# GFB_Sensorknoten.net
KiCad netlist of a schematic drawn in EAGLE
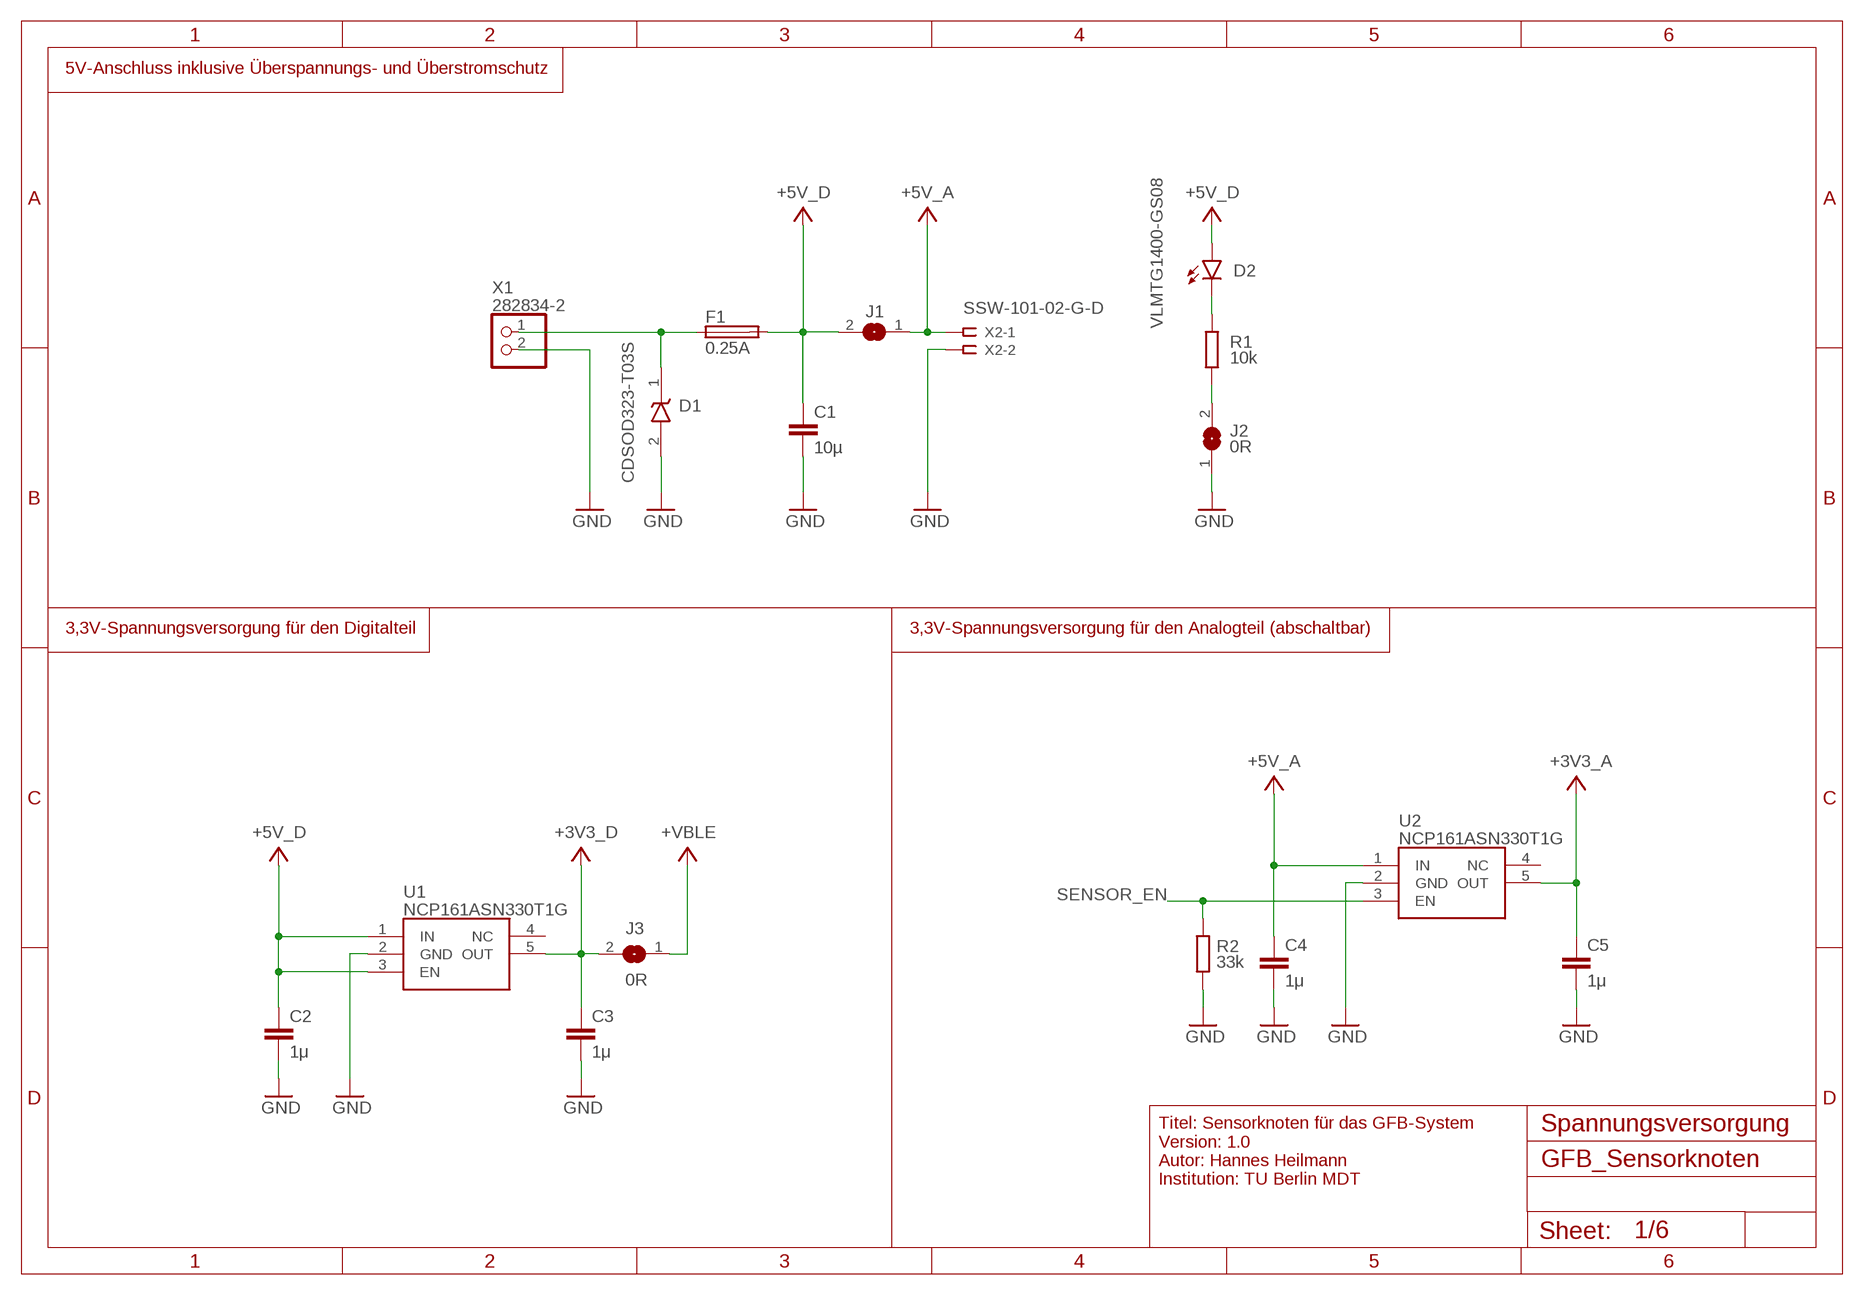
[diagram p0: schematic, sheet 1]
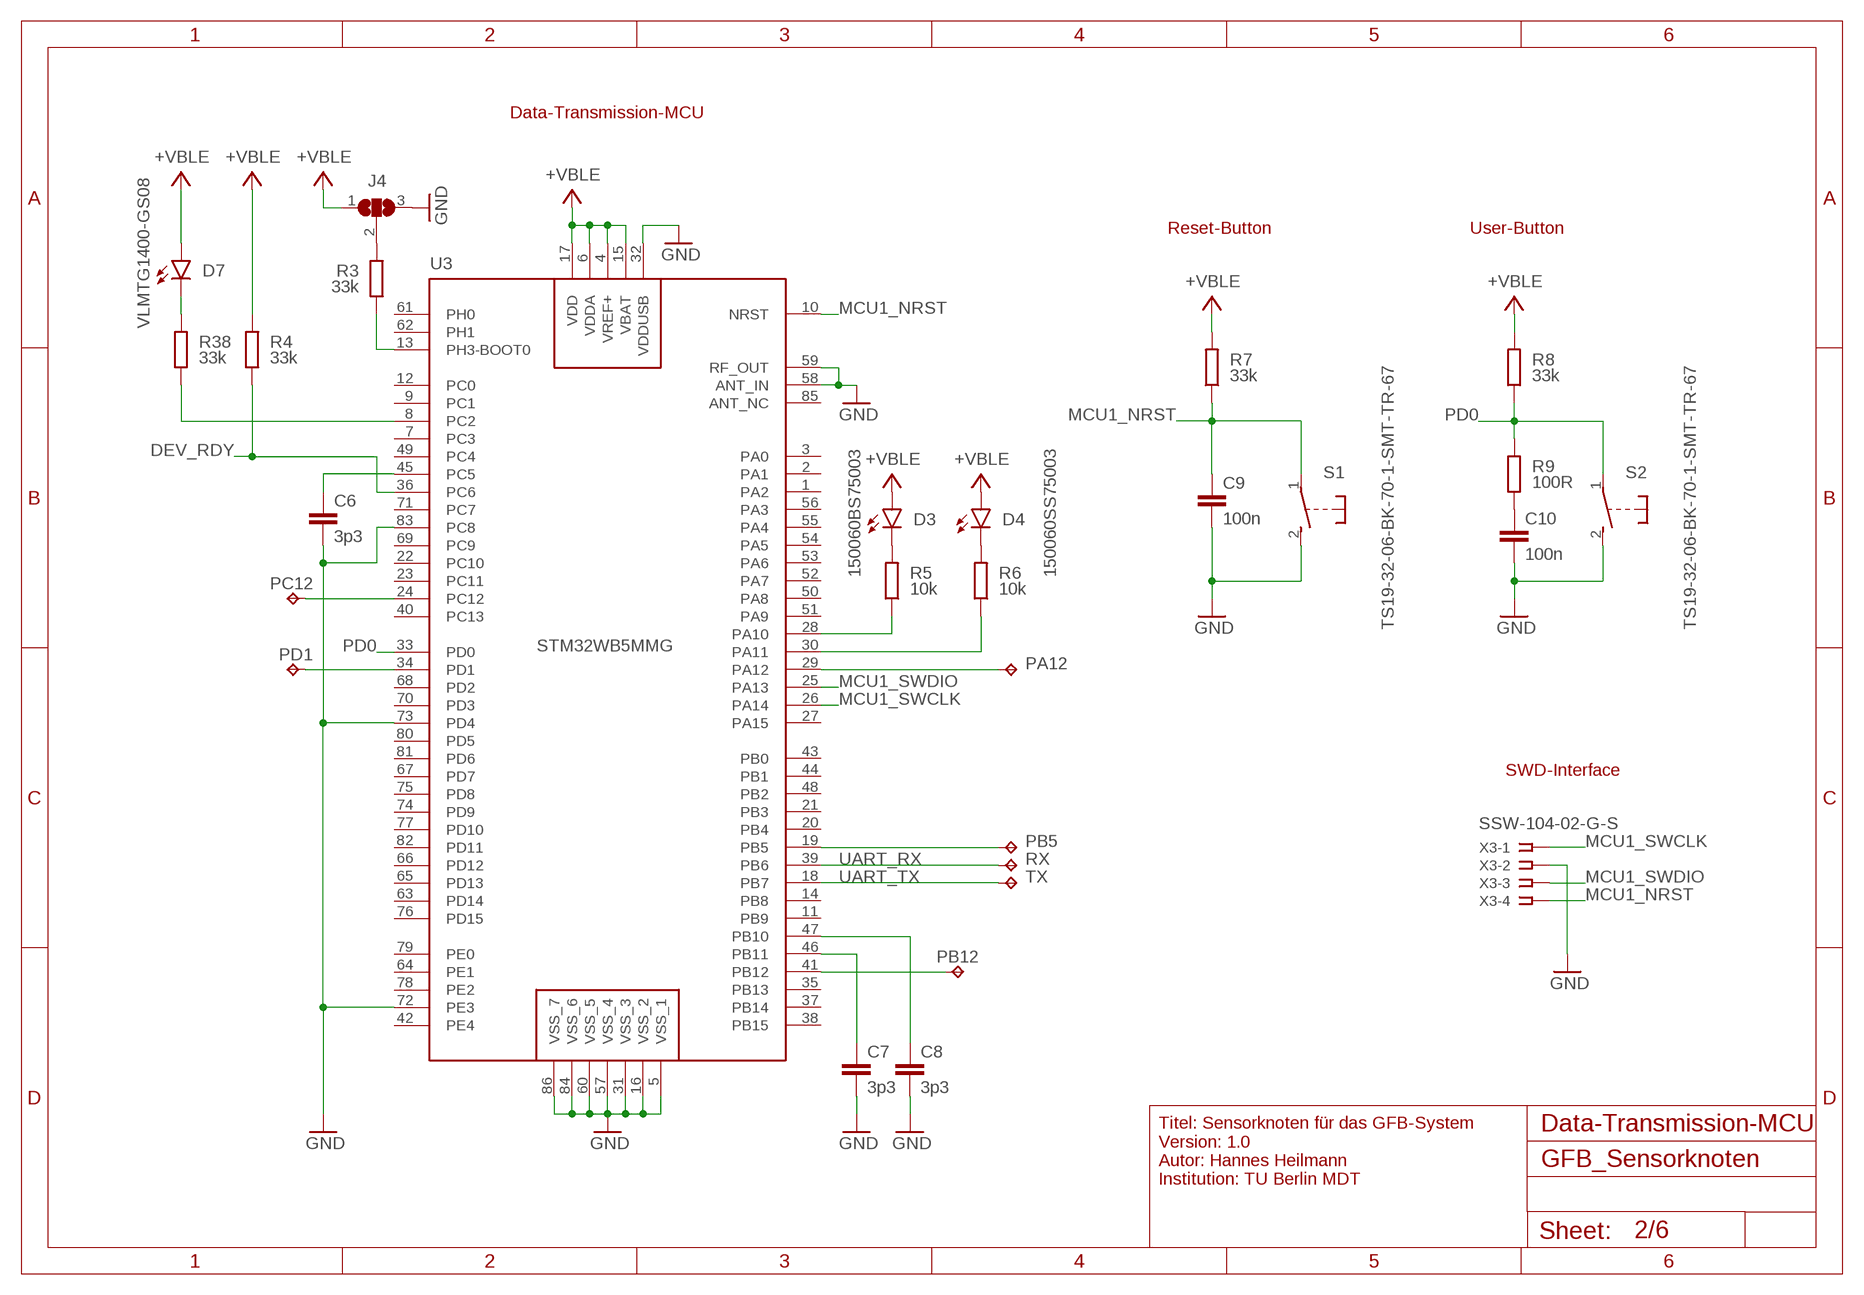
[diagram p1: schematic, sheet 2]
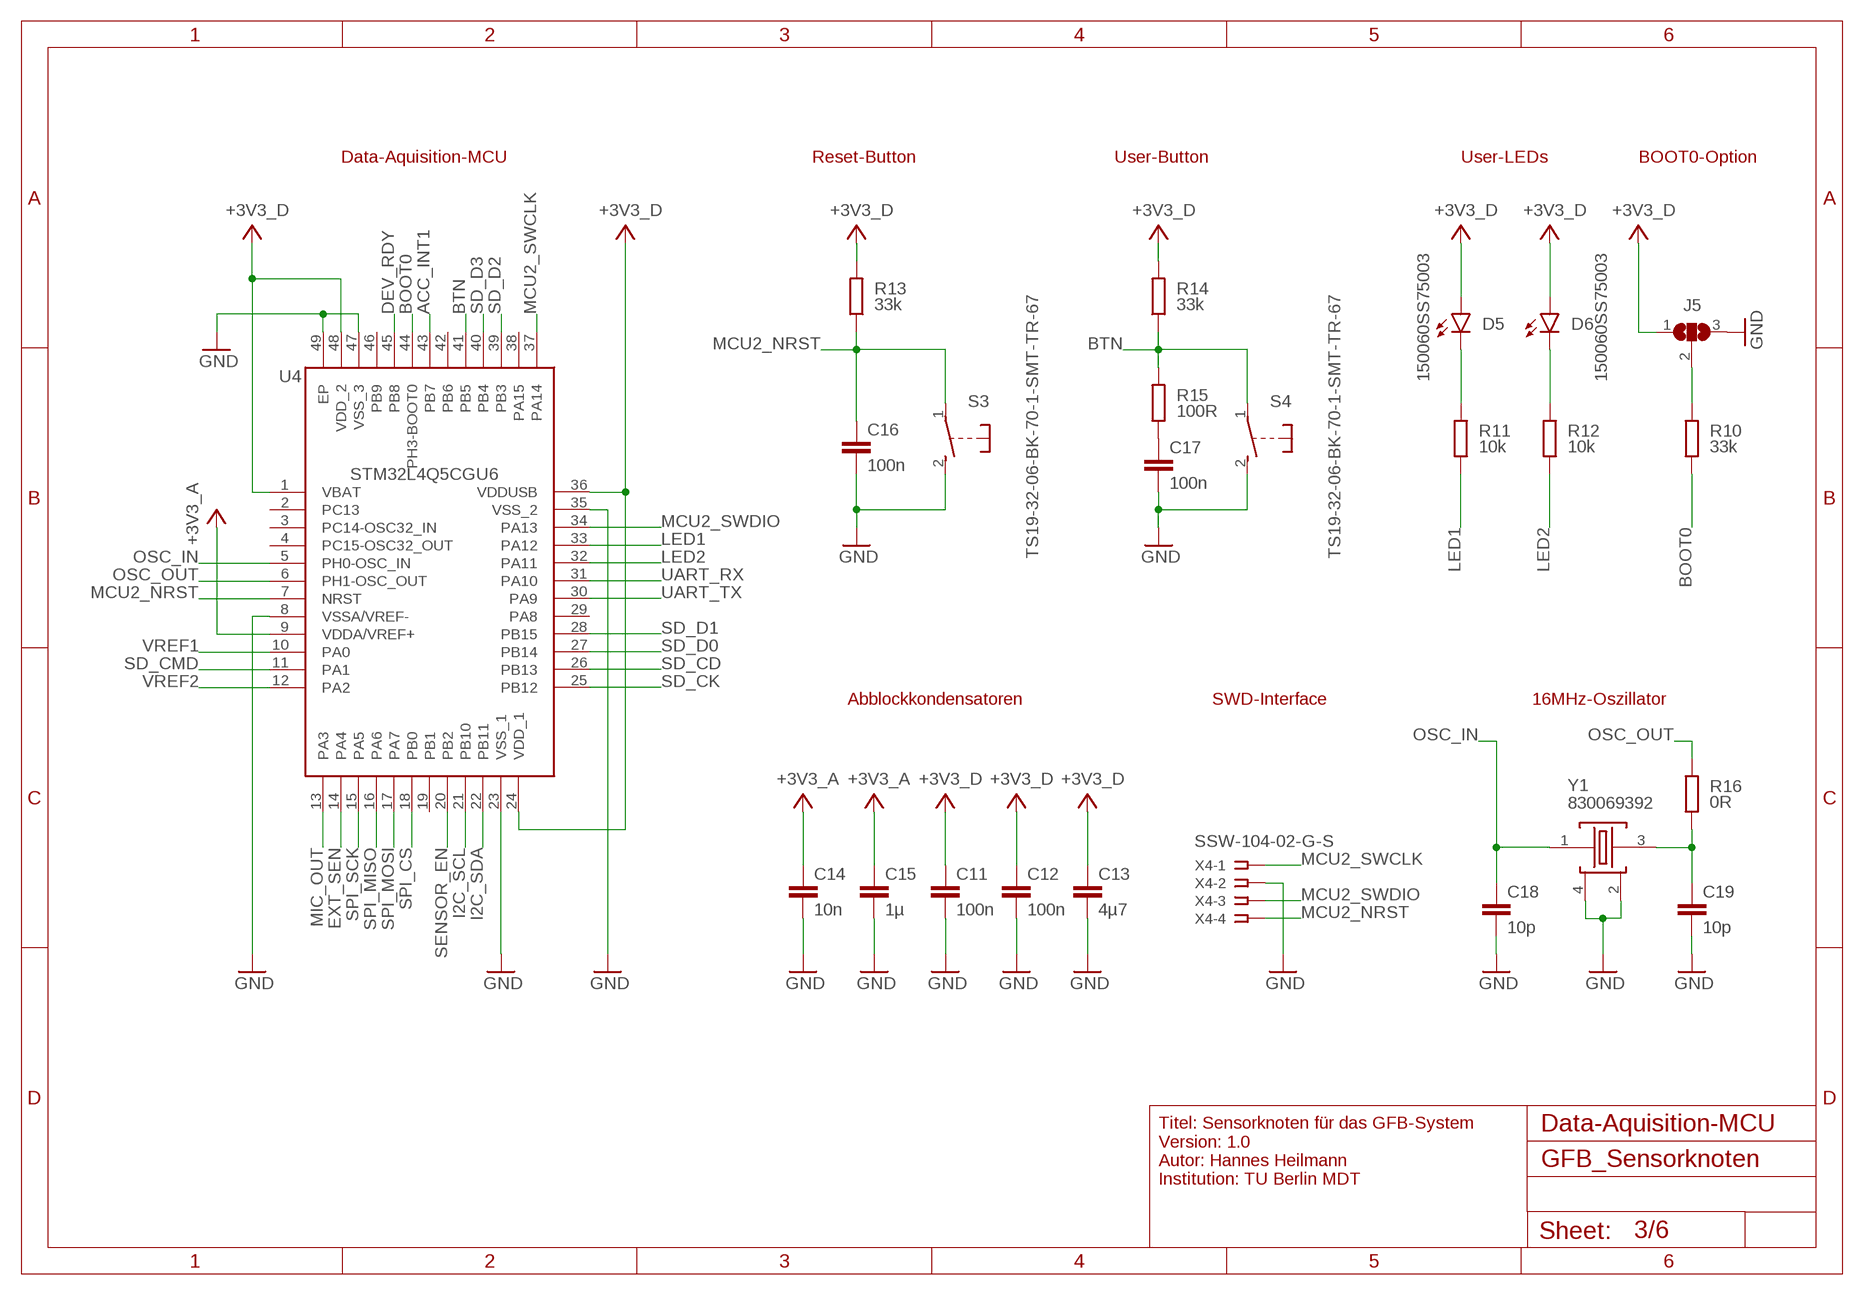
[diagram p2: schematic, sheet 3]
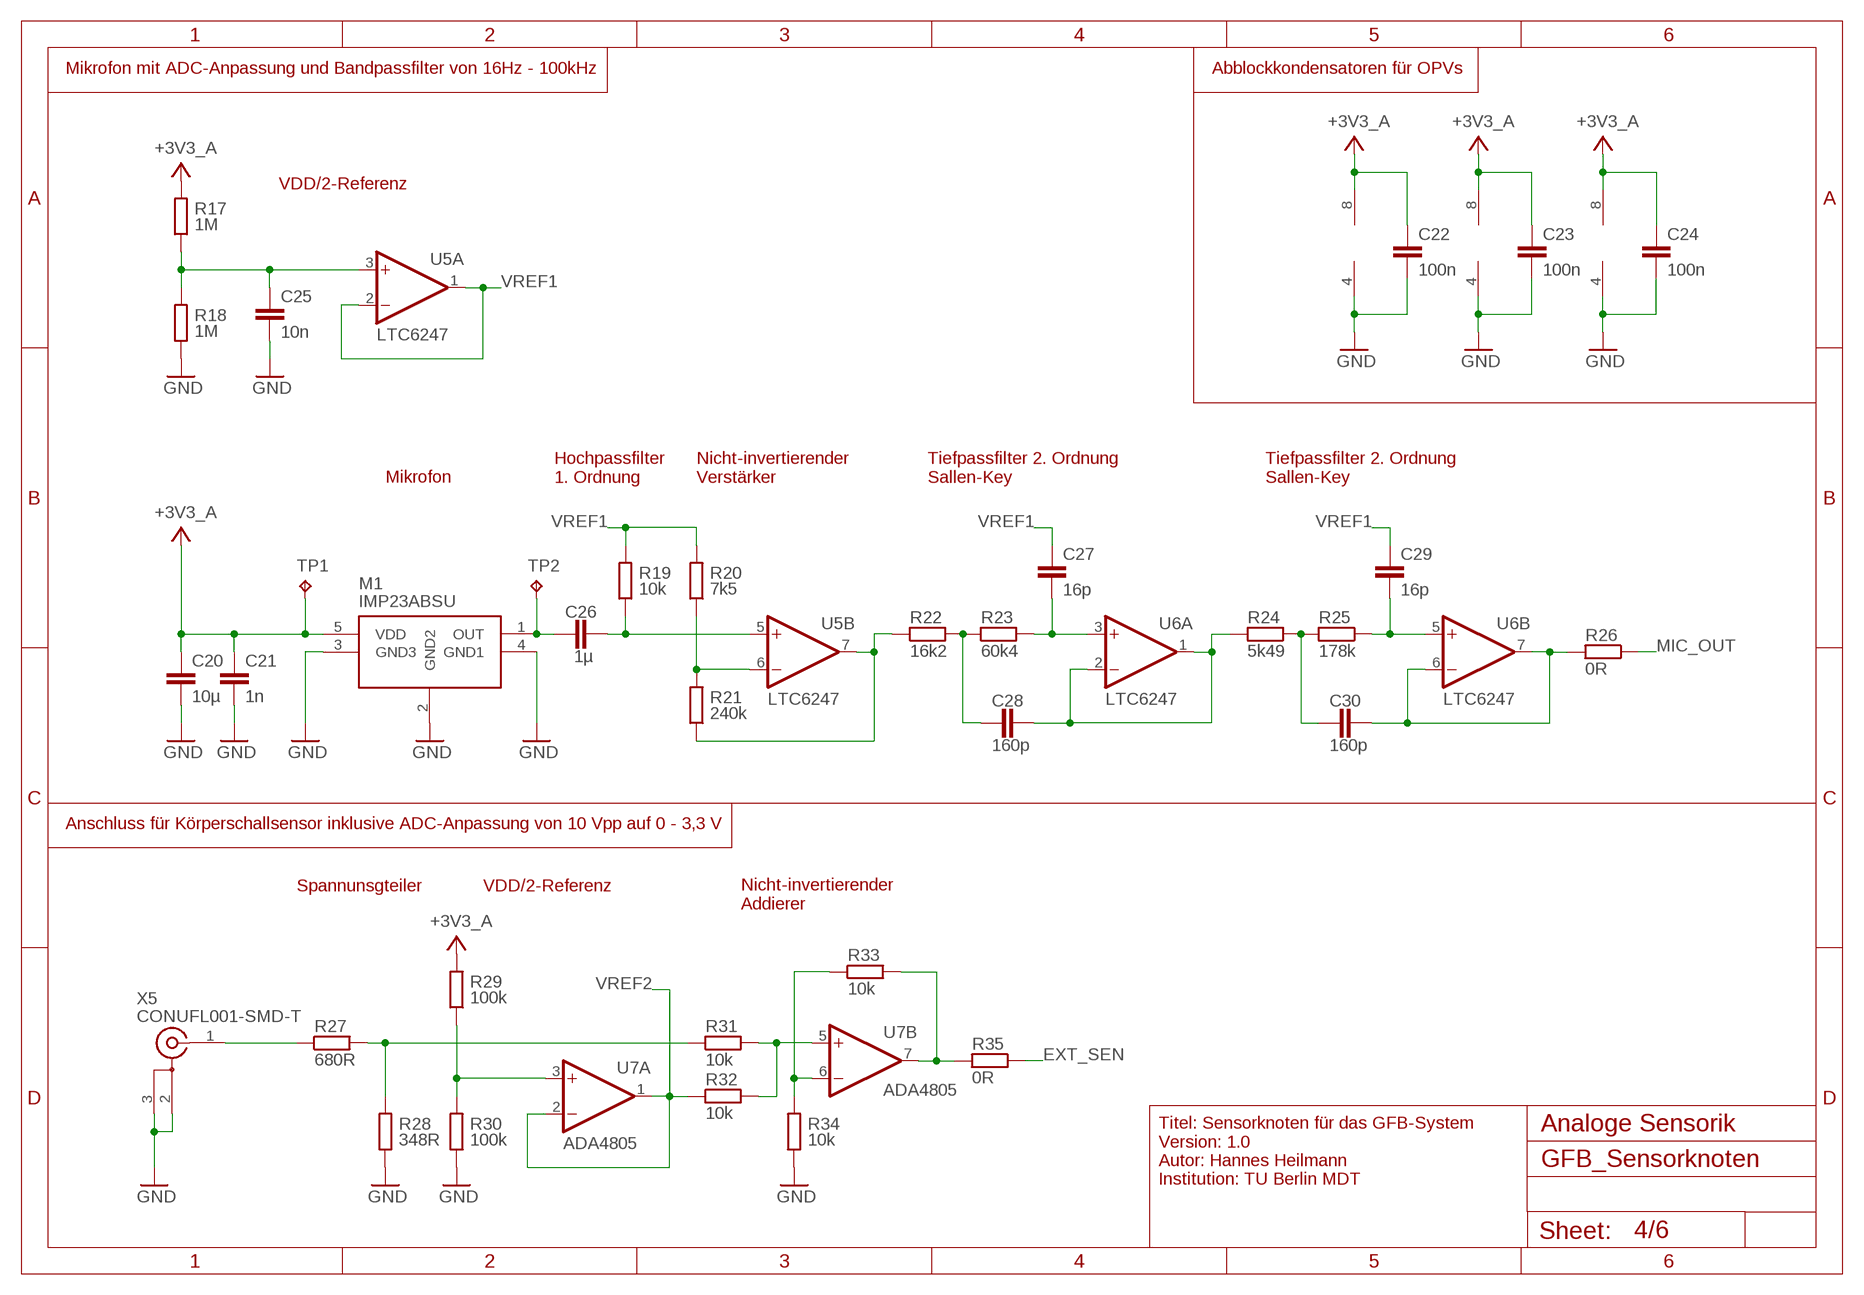
[diagram p3: schematic, sheet 4]
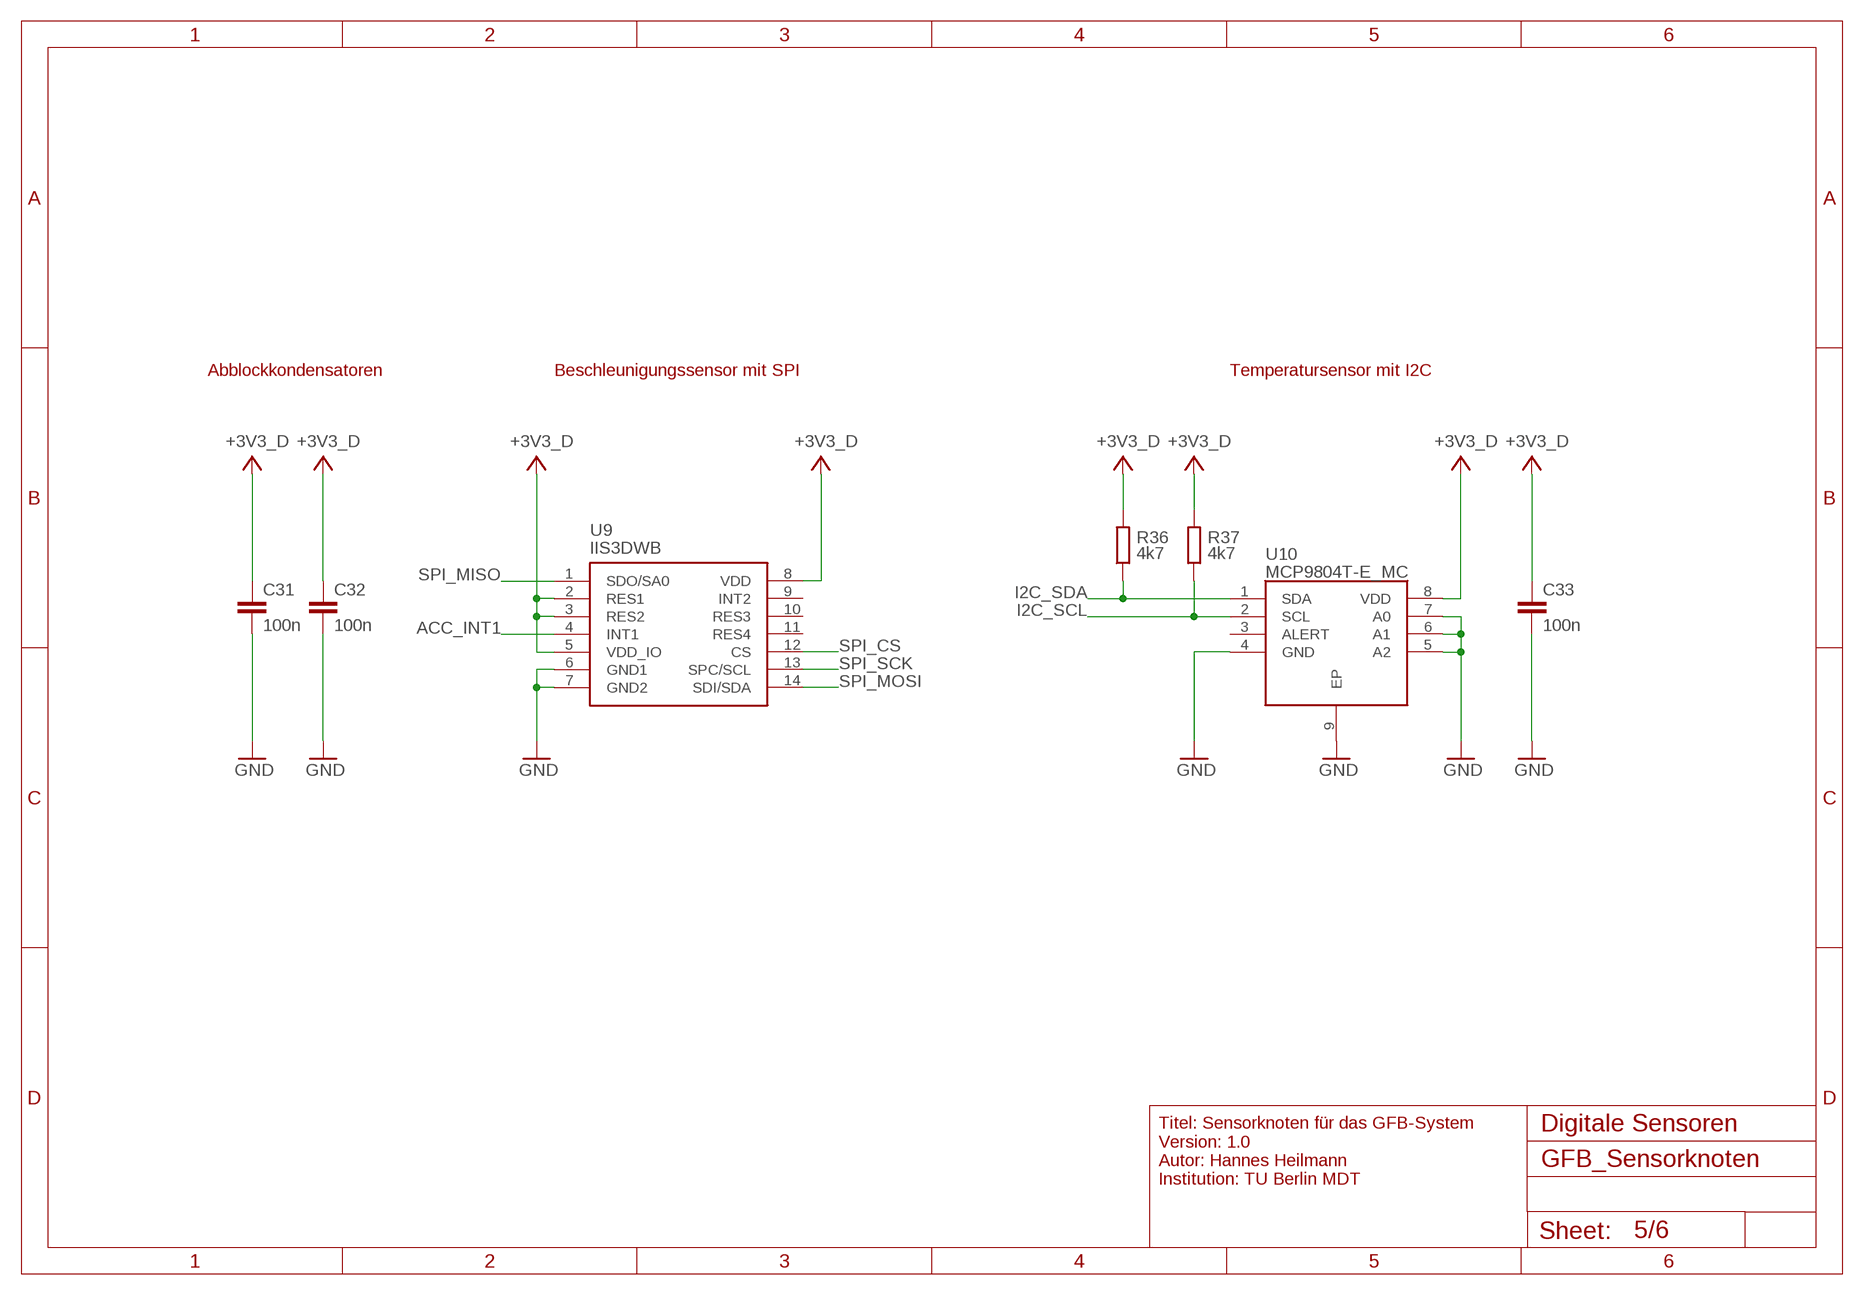
[diagram p4: schematic, sheet 5]
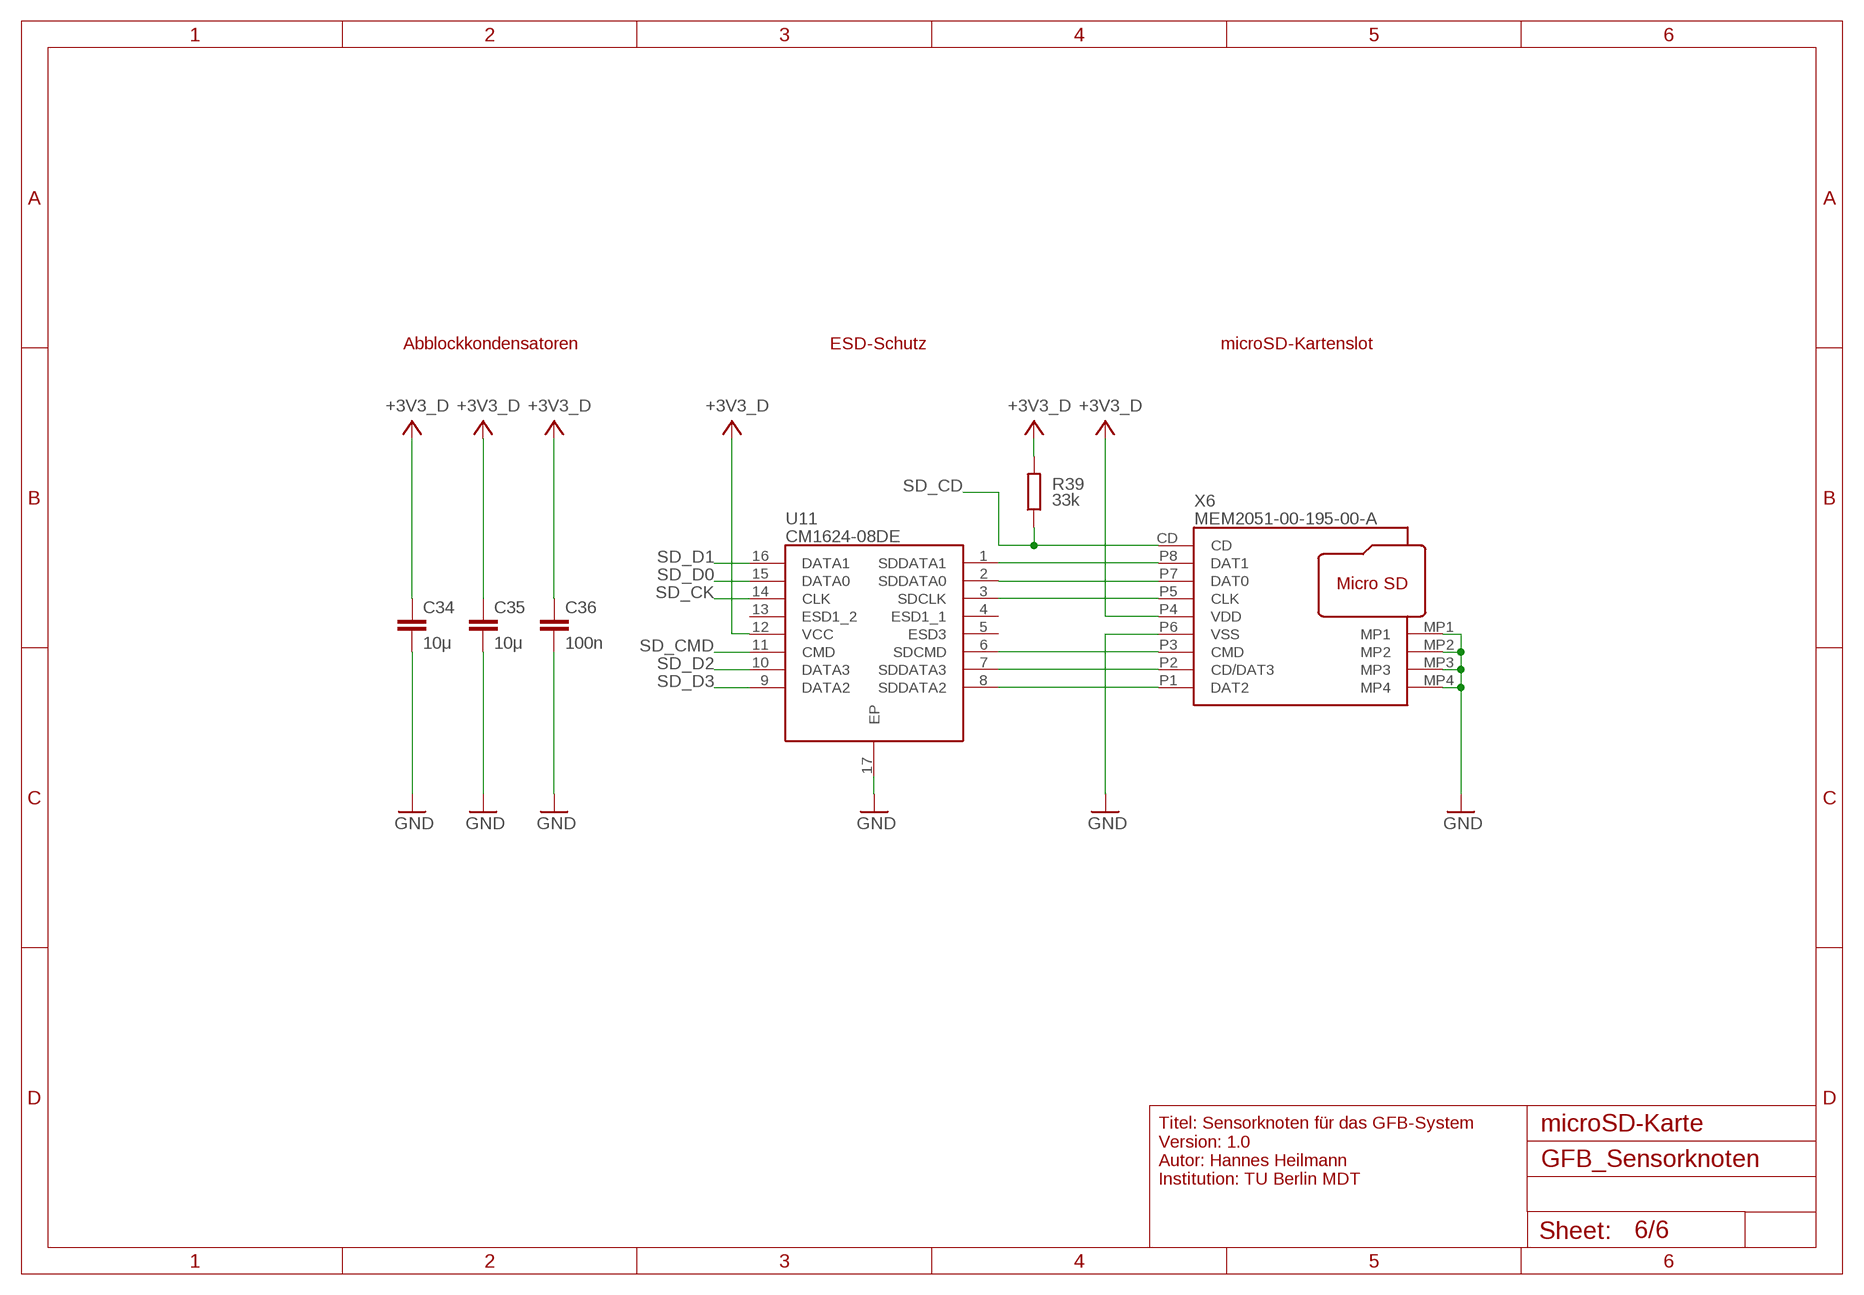
[diagram p5: schematic, sheet 6]

(export (version "E")
  (design (tool "Eeschema 10.0.6"))
  (components
    (comp (ref "C20")
      (value "10µ")
      (footprint "eagle-import:PATCHPOLYGRAPHV1_1608M")
      (libsource (lib "eagle-import") (part "C_OUTLINEC0603_OUTLINE"))
    )
    (comp (ref "C21")
      (value "1n")
      (footprint "eagle-import:PATCHPOLYGRAPHV1_1005M")
      (libsource (lib "eagle-import") (part "C_OUTLINEC0402_OUTLINE"))
    )
    (comp (ref "C22")
      (value "100n")
      (footprint "eagle-import:PATCHPOLYGRAPHV1_1005M")
      (libsource (lib "eagle-import") (part "C_OUTLINEC0402_OUTLINE"))
    )
    (comp (ref "C23")
      (value "100n")
      (footprint "eagle-import:PATCHPOLYGRAPHV1_1005M")
      (libsource (lib "eagle-import") (part "C_OUTLINEC0402_OUTLINE"))
    )
    (comp (ref "C24")
      (value "100n")
      (footprint "eagle-import:PATCHPOLYGRAPHV1_1005M")
      (libsource (lib "eagle-import") (part "C_OUTLINEC0402_OUTLINE"))
    )
    (comp (ref "C25")
      (value "10n")
      (footprint "eagle-import:PATCHPOLYGRAPHV1_1005M")
      (libsource (lib "eagle-import") (part "C_OUTLINEC0402_OUTLINE"))
    )
    (comp (ref "C26")
      (value "1µ")
      (footprint "eagle-import:PATCHPOLYGRAPHV1_1608M")
      (libsource (lib "eagle-import") (part "C_OUTLINEC0603_OUTLINE"))
    )
    (comp (ref "C27")
      (value "16p")
      (footprint "eagle-import:PATCHPOLYGRAPHV1_1005M")
      (libsource (lib "eagle-import") (part "C_OUTLINEC0402_OUTLINE"))
    )
    (comp (ref "C28")
      (value "160p")
      (footprint "eagle-import:PATCHPOLYGRAPHV1_1005M")
      (libsource (lib "eagle-import") (part "C_OUTLINEC0402_OUTLINE"))
    )
    (comp (ref "C29")
      (value "16p")
      (footprint "eagle-import:PATCHPOLYGRAPHV1_1005M")
      (libsource (lib "eagle-import") (part "C_OUTLINEC0402_OUTLINE"))
    )
    (comp (ref "C30")
      (value "160p")
      (footprint "eagle-import:PATCHPOLYGRAPHV1_1005M")
      (libsource (lib "eagle-import") (part "C_OUTLINEC0402_OUTLINE"))
    )
    (comp (ref "M1")
      (value "IMP23ABSU")
      (footprint "eagle-import:IMP23ABSU")
      (libsource (lib "eagle-import") (part "IMP23ABSU"))
    )
    (comp (ref "R17")
      (value "1M")
      (footprint "eagle-import:PATCHPOLYGRAPHV1_1005M")
      (libsource (lib "eagle-import") (part "R_OUTLINER0402_OUTLINE"))
    )
    (comp (ref "R18")
      (value "1M")
      (footprint "eagle-import:PATCHPOLYGRAPHV1_1005M")
      (libsource (lib "eagle-import") (part "R_OUTLINER0402_OUTLINE"))
    )
    (comp (ref "R19")
      (value "10k")
      (footprint "eagle-import:PATCHPOLYGRAPHV1_1005M")
      (libsource (lib "eagle-import") (part "R_OUTLINER0402_OUTLINE"))
    )
    (comp (ref "R20")
      (value "7k5")
      (footprint "eagle-import:PATCHPOLYGRAPHV1_1005M")
      (libsource (lib "eagle-import") (part "R_OUTLINER0402_OUTLINE"))
    )
    (comp (ref "R21")
      (value "240k")
      (footprint "eagle-import:PATCHPOLYGRAPHV1_1005M")
      (libsource (lib "eagle-import") (part "R_OUTLINER0402_OUTLINE"))
    )
    (comp (ref "R22")
      (value "16k2")
      (footprint "eagle-import:PATCHPOLYGRAPHV1_1005M")
      (libsource (lib "eagle-import") (part "R_OUTLINER0402_OUTLINE"))
    )
    (comp (ref "R23")
      (value "60k4")
      (footprint "eagle-import:PATCHPOLYGRAPHV1_1005M")
      (libsource (lib "eagle-import") (part "R_OUTLINER0402_OUTLINE"))
    )
    (comp (ref "R24")
      (value "5k49")
      (footprint "eagle-import:PATCHPOLYGRAPHV1_1005M")
      (libsource (lib "eagle-import") (part "R_OUTLINER0402_OUTLINE"))
    )
    (comp (ref "R25")
      (value "178k")
      (footprint "eagle-import:PATCHPOLYGRAPHV1_1005M")
      (libsource (lib "eagle-import") (part "R_OUTLINER0402_OUTLINE"))
    )
    (comp (ref "R26")
      (value "0R")
      (footprint "eagle-import:PATCHPOLYGRAPHV1_1005M")
      (libsource (lib "eagle-import") (part "R_OUTLINER0402_OUTLINE"))
    )
    (comp (ref "R27")
      (value "680R")
      (footprint "eagle-import:PATCHPOLYGRAPHV1_1005M")
      (libsource (lib "eagle-import") (part "R_OUTLINER0402_OUTLINE"))
    )
    (comp (ref "R28")
      (value "348R")
      (footprint "eagle-import:PATCHPOLYGRAPHV1_1005M")
      (libsource (lib "eagle-import") (part "R_OUTLINER0402_OUTLINE"))
    )
    (comp (ref "R29")
      (value "100k")
      (footprint "eagle-import:PATCHPOLYGRAPHV1_1005M")
      (libsource (lib "eagle-import") (part "R_OUTLINER0402_OUTLINE"))
    )
    (comp (ref "R30")
      (value "100k")
      (footprint "eagle-import:PATCHPOLYGRAPHV1_1005M")
      (libsource (lib "eagle-import") (part "R_OUTLINER0402_OUTLINE"))
    )
    (comp (ref "R31")
      (value "10k")
      (footprint "eagle-import:PATCHPOLYGRAPHV1_1005M")
      (libsource (lib "eagle-import") (part "R_OUTLINER0402_OUTLINE"))
    )
    (comp (ref "R32")
      (value "10k")
      (footprint "eagle-import:PATCHPOLYGRAPHV1_1005M")
      (libsource (lib "eagle-import") (part "R_OUTLINER0402_OUTLINE"))
    )
    (comp (ref "R33")
      (value "10k")
      (footprint "eagle-import:PATCHPOLYGRAPHV1_1005M")
      (libsource (lib "eagle-import") (part "R_OUTLINER0402_OUTLINE"))
    )
    (comp (ref "R34")
      (value "10k")
      (footprint "eagle-import:PATCHPOLYGRAPHV1_1005M")
      (libsource (lib "eagle-import") (part "R_OUTLINER0402_OUTLINE"))
    )
    (comp (ref "R35")
      (value "0R")
      (footprint "eagle-import:PATCHPOLYGRAPHV1_1005M")
      (libsource (lib "eagle-import") (part "R_OUTLINER0402_OUTLINE"))
    )
    (comp (ref "TP1")
      (value "TPTP06R")
      (footprint "eagle-import:TP06R")
      (libsource (lib "eagle-import") (part "TPTP06R"))
    )
    (comp (ref "TP2")
      (value "TPTP06R")
      (footprint "eagle-import:TP06R")
      (libsource (lib "eagle-import") (part "TPTP06R"))
    )
    (comp (ref "U5")
      (value "LTC6247")
      (footprint "eagle-import:SOP65P490X110-8N")
      (libsource (lib "eagle-import") (part "LTC6247CMS8#PBF"))
    )
    (comp (ref "U6")
      (value "LTC6247")
      (footprint "eagle-import:SOP65P490X110-8N")
      (libsource (lib "eagle-import") (part "LTC6247CMS8#PBF"))
    )
    (comp (ref "U7")
      (value "ADA4805")
      (footprint "eagle-import:SOP65P490X110-8N")
      (libsource (lib "eagle-import") (part "ADA4805-2ARMZ-R7"))
    )
    (comp (ref "X5")
      (value "CONUFL001-SMD-T")
      (footprint "eagle-import:CONUFL001-SMD")
      (fields (field (name "MOUSER_PART_NUMBER") "712-CONUFL001-SMD-T"))
      (libsource (lib "eagle-import") (part "CONUFL001-SMD-T"))
    )
    (comp (ref "C11")
      (value "100n")
      (footprint "eagle-import:PATCHPOLYGRAPHV1_1005M")
      (libsource (lib "eagle-import") (part "C_OUTLINEC0402_OUTLINE"))
    )
    (comp (ref "C12")
      (value "100n")
      (footprint "eagle-import:PATCHPOLYGRAPHV1_1005M")
      (libsource (lib "eagle-import") (part "C_OUTLINEC0402_OUTLINE"))
    )
    (comp (ref "C13")
      (value "4µ7")
      (footprint "eagle-import:PATCHPOLYGRAPHV1_1608M")
      (libsource (lib "eagle-import") (part "C_OUTLINEC0603_OUTLINE"))
    )
    (comp (ref "C14")
      (value "10n")
      (footprint "eagle-import:PATCHPOLYGRAPHV1_1005M")
      (libsource (lib "eagle-import") (part "C_OUTLINEC0402_OUTLINE"))
    )
    (comp (ref "C15")
      (value "1µ")
      (footprint "eagle-import:PATCHPOLYGRAPHV1_1608M")
      (libsource (lib "eagle-import") (part "C_OUTLINEC0603_OUTLINE"))
    )
    (comp (ref "C16")
      (value "100n")
      (footprint "eagle-import:PATCHPOLYGRAPHV1_1005M")
      (libsource (lib "eagle-import") (part "C_OUTLINEC0402_OUTLINE"))
    )
    (comp (ref "C17")
      (value "100n")
      (footprint "eagle-import:PATCHPOLYGRAPHV1_1005M")
      (libsource (lib "eagle-import") (part "C_OUTLINEC0402_OUTLINE"))
    )
    (comp (ref "C18")
      (value "10p")
      (footprint "eagle-import:PATCHPOLYGRAPHV1_1005M")
      (libsource (lib "eagle-import") (part "C_OUTLINEC0402_OUTLINE"))
    )
    (comp (ref "C19")
      (value "10p")
      (footprint "eagle-import:PATCHPOLYGRAPHV1_1005M")
      (libsource (lib "eagle-import") (part "C_OUTLINEC0402_OUTLINE"))
    )
    (comp (ref "D5")
      (value "150060SS75003")
      (footprint "eagle-import:CHIP-LED0603")
      (libsource (lib "eagle-import") (part "LEDCHIP-LED0603"))
    )
    (comp (ref "D6")
      (value "150060SS75003")
      (footprint "eagle-import:CHIP-LED0603")
      (libsource (lib "eagle-import") (part "LEDCHIP-LED0603"))
    )
    (comp (ref "J5")
      (value "JUMPER_3JUMPER_3_0402")
      (footprint "eagle-import:JUMPER_3_0402")
      (libsource (lib "eagle-import") (part "JUMPER_3JUMPER_3_0402"))
    )
    (comp (ref "R10")
      (value "33k")
      (footprint "eagle-import:PATCHPOLYGRAPHV1_1005M")
      (libsource (lib "eagle-import") (part "R_OUTLINER0402_OUTLINE"))
    )
    (comp (ref "R11")
      (value "10k")
      (footprint "eagle-import:PATCHPOLYGRAPHV1_1005M")
      (libsource (lib "eagle-import") (part "R_OUTLINER0402_OUTLINE"))
    )
    (comp (ref "R12")
      (value "10k")
      (footprint "eagle-import:PATCHPOLYGRAPHV1_1005M")
      (libsource (lib "eagle-import") (part "R_OUTLINER0402_OUTLINE"))
    )
    (comp (ref "R13")
      (value "33k")
      (footprint "eagle-import:PATCHPOLYGRAPHV1_1005M")
      (libsource (lib "eagle-import") (part "R_OUTLINER0402_OUTLINE"))
    )
    (comp (ref "R14")
      (value "33k")
      (footprint "eagle-import:PATCHPOLYGRAPHV1_1005M")
      (libsource (lib "eagle-import") (part "R_OUTLINER0402_OUTLINE"))
    )
    (comp (ref "R15")
      (value "100R")
      (footprint "eagle-import:PATCHPOLYGRAPHV1_1005M")
      (libsource (lib "eagle-import") (part "R_OUTLINER0402_OUTLINE"))
    )
    (comp (ref "R16")
      (value "0R")
      (footprint "eagle-import:PATCHPOLYGRAPHV1_1005M")
      (libsource (lib "eagle-import") (part "R_OUTLINER0402_OUTLINE"))
    )
    (comp (ref "S3")
      (value "TS19-32-06-BK-70-1-SMT-TR-67")
      (footprint "eagle-import:TS193206BK701SMTTR67")
      (fields (field (name "MOUSER_PART_NUMBER") "179-TS193206BK701SM"))
      (libsource (lib "eagle-import") (part "TS19-32-06-BK-70-1-SMT-TR-67"))
    )
    (comp (ref "S4")
      (value "TS19-32-06-BK-70-1-SMT-TR-67")
      (footprint "eagle-import:TS193206BK701SMTTR67")
      (fields (field (name "MOUSER_PART_NUMBER") "179-TS193206BK701SM"))
      (libsource (lib "eagle-import") (part "TS19-32-06-BK-70-1-SMT-TR-67"))
    )
    (comp (ref "U4")
      (value "STM32L4Q5CGU6")
      (footprint "eagle-import:QFN50P700X700X65-49N")
      (fields (field (name "MOUSER_PART_NUMBER") "511-STM32L4Q5CGU6"))
      (libsource (lib "eagle-import") (part "STM32L4Q5CGU6"))
    )
    (comp (ref "X4")
      (value "SSW-104-02-G-S")
      (footprint "eagle-import:SSW-104-02-G-S")
      (fields (field (name "MF") "Samtec Inc."))
      (libsource (lib "eagle-import") (part "SSW-104-02-G-S"))
    )
    (comp (ref "Y1")
      (value "830069392")
      (footprint "eagle-import:830069392")
      (fields
        (field (name "MANUFACTURER_PART_NUMBER") "830069395")
        (field (name "MOUSER_PART_NUMBER") "710-830069395")
      )
      (libsource (lib "eagle-import") (part "830069392"))
    )
    (comp (ref "C1")
      (value "10µ")
      (footprint "eagle-import:PATCHPOLYGRAPHV1_1608M")
      (libsource (lib "eagle-import") (part "C_OUTLINEC0603_OUTLINE"))
    )
    (comp (ref "C2")
      (value "1μ")
      (footprint "eagle-import:PATCHPOLYGRAPHV1_1608M")
      (libsource (lib "eagle-import") (part "C_OUTLINEC0603_OUTLINE"))
    )
    (comp (ref "C3")
      (value "1μ")
      (footprint "eagle-import:PATCHPOLYGRAPHV1_1608M")
      (libsource (lib "eagle-import") (part "C_OUTLINEC0603_OUTLINE"))
    )
    (comp (ref "C4")
      (value "1μ")
      (footprint "eagle-import:PATCHPOLYGRAPHV1_1608M")
      (libsource (lib "eagle-import") (part "C_OUTLINEC0603_OUTLINE"))
    )
    (comp (ref "C5")
      (value "1μ")
      (footprint "eagle-import:PATCHPOLYGRAPHV1_1608M")
      (libsource (lib "eagle-import") (part "C_OUTLINEC0603_OUTLINE"))
    )
    (comp (ref "D1")
      (value "CDSOD323-T03S")
      (footprint "eagle-import:SOD2513X114N")
      (fields (field (name "MOUSER_PART_NUMBER") "652-CDSOD323-T03S"))
      (libsource (lib "eagle-import") (part "CDSOD323-T03S"))
    )
    (comp (ref "D2")
      (value "VLMTG1400-GS08")
      (footprint "eagle-import:CHIP-LED0603")
      (libsource (lib "eagle-import") (part "LEDCHIP-LED0603"))
    )
    (comp (ref "F1")
      (value "SF-0603FP025F-2")
      (footprint "eagle-import:R0603")
      (libsource (lib "eagle-import") (part "SF-0603FP025F-2"))
    )
    (comp (ref "J1") (value "SJ") (footprint "eagle-import:SJ") (libsource (lib "eagle-import") (part "SJ")))
    (comp (ref "J2")
      (value "0R")
      (footprint "eagle-import:PATCHPOLYGRAPHV1_1005M")
      (libsource (lib "eagle-import") (part "JUMPER_0402"))
    )
    (comp (ref "J3")
      (value "0R")
      (footprint "eagle-import:PATCHPOLYGRAPHV1_1005M")
      (libsource (lib "eagle-import") (part "JUMPER_0402"))
    )
    (comp (ref "R1")
      (value "10k")
      (footprint "eagle-import:PATCHPOLYGRAPHV1_1005M")
      (libsource (lib "eagle-import") (part "R_OUTLINER0402_OUTLINE"))
    )
    (comp (ref "R2")
      (value "33k")
      (footprint "eagle-import:PATCHPOLYGRAPHV1_1005M")
      (libsource (lib "eagle-import") (part "R_OUTLINER0402_OUTLINE"))
    )
    (comp (ref "U1")
      (value "NCP161ASN330T1G")
      (footprint "eagle-import:SOT95P280X145-5N")
      (fields (field (name "MOUSER_PART_NUMBER") "863-NCP161ASN330T1G"))
      (libsource (lib "eagle-import") (part "NCP161ASN330T1G"))
    )
    (comp (ref "U2")
      (value "NCP161ASN330T1G")
      (footprint "eagle-import:SOT95P280X145-5N")
      (fields (field (name "MOUSER_PART_NUMBER") "863-NCP161ASN330T1G"))
      (libsource (lib "eagle-import") (part "NCP161ASN330T1G"))
    )
    (comp (ref "X1")
      (value "282834-2")
      (footprint "eagle-import:SHDR2W85P0X254_1X2_554X650X103")
      (libsource (lib "eagle-import") (part "282834-2"))
    )
    (comp (ref "X2")
      (value "SSW-101-02-G-D")
      (footprint "eagle-import:SSW-101-02-G-D")
      (fields (field (name "MF") "Samtec Inc."))
      (libsource (lib "eagle-import") (part "SSW-101-02-G-D"))
    )
    (comp (ref "C31")
      (value "100n")
      (footprint "eagle-import:PATCHPOLYGRAPHV1_1005M")
      (libsource (lib "eagle-import") (part "C_OUTLINEC0402_OUTLINE"))
    )
    (comp (ref "C32")
      (value "100n")
      (footprint "eagle-import:PATCHPOLYGRAPHV1_1005M")
      (libsource (lib "eagle-import") (part "C_OUTLINEC0402_OUTLINE"))
    )
    (comp (ref "C33")
      (value "100n")
      (footprint "eagle-import:PATCHPOLYGRAPHV1_1005M")
      (libsource (lib "eagle-import") (part "C_OUTLINEC0402_OUTLINE"))
    )
    (comp (ref "R36")
      (value "4k7")
      (footprint "eagle-import:PATCHPOLYGRAPHV1_1005M")
      (libsource (lib "eagle-import") (part "R_OUTLINER0402_OUTLINE"))
    )
    (comp (ref "R37")
      (value "4k7")
      (footprint "eagle-import:PATCHPOLYGRAPHV1_1005M")
      (libsource (lib "eagle-import") (part "R_OUTLINER0402_OUTLINE"))
    )
    (comp (ref "U9")
      (value "IIS3DWB")
      (footprint "eagle-import:IIS3DWB")
      (libsource (lib "eagle-import") (part "IIS3DWB"))
    )
    (comp (ref "U10")
      (value "MCP9804T-E_MC")
      (footprint "eagle-import:SON50P300X200X100-9N")
      (fields
        (field (name "ARROW_PART_NUMBER") "MCP9804T-E/MC")
        (field (name "MOUSER_PART_NUMBER") "579-MCP9804T-E/MC")
      )
      (libsource (lib "eagle-import") (part "MCP9804T-E_MC"))
    )
    (comp (ref "C6")
      (value "3p3")
      (footprint "eagle-import:PATCHPOLYGRAPHV1_1005M")
      (libsource (lib "eagle-import") (part "C_OUTLINEC0402_OUTLINE"))
    )
    (comp (ref "C7")
      (value "3p3")
      (footprint "eagle-import:PATCHPOLYGRAPHV1_1005M")
      (libsource (lib "eagle-import") (part "C_OUTLINEC0402_OUTLINE"))
    )
    (comp (ref "C8")
      (value "3p3")
      (footprint "eagle-import:PATCHPOLYGRAPHV1_1005M")
      (libsource (lib "eagle-import") (part "C_OUTLINEC0402_OUTLINE"))
    )
    (comp (ref "C9")
      (value "100n")
      (footprint "eagle-import:PATCHPOLYGRAPHV1_1005M")
      (libsource (lib "eagle-import") (part "C_OUTLINEC0402_OUTLINE"))
    )
    (comp (ref "C10")
      (value "100n")
      (footprint "eagle-import:PATCHPOLYGRAPHV1_1005M")
      (libsource (lib "eagle-import") (part "C_OUTLINEC0402_OUTLINE"))
    )
    (comp (ref "D3")
      (value "150060BS75003")
      (footprint "eagle-import:CHIP-LED0603")
      (libsource (lib "eagle-import") (part "LEDCHIP-LED0603"))
    )
    (comp (ref "D4")
      (value "150060SS75003")
      (footprint "eagle-import:CHIP-LED0603")
      (libsource (lib "eagle-import") (part "LEDCHIP-LED0603"))
    )
    (comp (ref "D7")
      (value "VLMTG1400-GS08")
      (footprint "eagle-import:CHIP-LED0603")
      (libsource (lib "eagle-import") (part "LEDCHIP-LED0603"))
    )
    (comp (ref "J4")
      (value "JUMPER_3JUMPER_3_0402")
      (footprint "eagle-import:JUMPER_3_0402")
      (libsource (lib "eagle-import") (part "JUMPER_3JUMPER_3_0402"))
    )
    (comp (ref "PA12")
      (value "TPTP06R")
      (footprint "eagle-import:TP06R")
      (libsource (lib "eagle-import") (part "TPTP06R"))
    )
    (comp (ref "PB5")
      (value "TPTP06R")
      (footprint "eagle-import:TP06R")
      (libsource (lib "eagle-import") (part "TPTP06R"))
    )
    (comp (ref "PB12")
      (value "TPTP06R")
      (footprint "eagle-import:TP06R")
      (libsource (lib "eagle-import") (part "TPTP06R"))
    )
    (comp (ref "PC12")
      (value "TPTP06R")
      (footprint "eagle-import:TP06R")
      (libsource (lib "eagle-import") (part "TPTP06R"))
    )
    (comp (ref "PD1")
      (value "TPTP06R")
      (footprint "eagle-import:TP06R")
      (libsource (lib "eagle-import") (part "TPTP06R"))
    )
    (comp (ref "R3")
      (value "33k")
      (footprint "eagle-import:PATCHPOLYGRAPHV1_1005M")
      (libsource (lib "eagle-import") (part "R_OUTLINER0402_OUTLINE"))
    )
    (comp (ref "R4")
      (value "33k")
      (footprint "eagle-import:PATCHPOLYGRAPHV1_1005M")
      (libsource (lib "eagle-import") (part "R_OUTLINER0402_OUTLINE"))
    )
    (comp (ref "R5")
      (value "10k")
      (footprint "eagle-import:PATCHPOLYGRAPHV1_1005M")
      (libsource (lib "eagle-import") (part "R_OUTLINER0402_OUTLINE"))
    )
    (comp (ref "R6")
      (value "10k")
      (footprint "eagle-import:PATCHPOLYGRAPHV1_1005M")
      (libsource (lib "eagle-import") (part "R_OUTLINER0402_OUTLINE"))
    )
    (comp (ref "R7")
      (value "33k")
      (footprint "eagle-import:PATCHPOLYGRAPHV1_1005M")
      (libsource (lib "eagle-import") (part "R_OUTLINER0402_OUTLINE"))
    )
    (comp (ref "R8")
      (value "33k")
      (footprint "eagle-import:PATCHPOLYGRAPHV1_1005M")
      (libsource (lib "eagle-import") (part "R_OUTLINER0402_OUTLINE"))
    )
    (comp (ref "R9")
      (value "100R")
      (footprint "eagle-import:PATCHPOLYGRAPHV1_1005M")
      (libsource (lib "eagle-import") (part "R_OUTLINER0402_OUTLINE"))
    )
    (comp (ref "R38")
      (value "33k")
      (footprint "eagle-import:PATCHPOLYGRAPHV1_1005M")
      (libsource (lib "eagle-import") (part "R_OUTLINER0402_OUTLINE"))
    )
    (comp (ref "RX")
      (value "TPTP06R")
      (footprint "eagle-import:TP06R")
      (libsource (lib "eagle-import") (part "TPTP06R"))
    )
    (comp (ref "S1")
      (value "TS19-32-06-BK-70-1-SMT-TR-67")
      (footprint "eagle-import:TS193206BK701SMTTR67")
      (fields (field (name "MOUSER_PART_NUMBER") "179-TS193206BK701SM"))
      (libsource (lib "eagle-import") (part "TS19-32-06-BK-70-1-SMT-TR-67"))
    )
    (comp (ref "S2")
      (value "TS19-32-06-BK-70-1-SMT-TR-67")
      (footprint "eagle-import:TS193206BK701SMTTR67")
      (fields (field (name "MOUSER_PART_NUMBER") "179-TS193206BK701SM"))
      (libsource (lib "eagle-import") (part "TS19-32-06-BK-70-1-SMT-TR-67"))
    )
    (comp (ref "TX")
      (value "TPTP06R")
      (footprint "eagle-import:TP06R")
      (libsource (lib "eagle-import") (part "TPTP06R"))
    )
    (comp (ref "U3")
      (value "STM32WB5MMG")
      (footprint "eagle-import:STM32WB5MMG")
      (libsource (lib "eagle-import") (part "STM32WB5MMG"))
    )
    (comp (ref "X3")
      (value "SSW-104-02-G-S")
      (footprint "eagle-import:SSW-104-02-G-S")
      (fields (field (name "MF") "Samtec Inc."))
      (libsource (lib "eagle-import") (part "SSW-104-02-G-S"))
    )
    (comp (ref "C34")
      (value "10μ")
      (footprint "eagle-import:PATCHPOLYGRAPHV1_1608M")
      (libsource (lib "eagle-import") (part "C_OUTLINEC0603_OUTLINE"))
    )
    (comp (ref "C35")
      (value "10μ")
      (footprint "eagle-import:PATCHPOLYGRAPHV1_1608M")
      (libsource (lib "eagle-import") (part "C_OUTLINEC0603_OUTLINE"))
    )
    (comp (ref "C36")
      (value "100n")
      (footprint "eagle-import:PATCHPOLYGRAPHV1_1005M")
      (libsource (lib "eagle-import") (part "C_OUTLINEC0402_OUTLINE"))
    )
    (comp (ref "R39")
      (value "33k")
      (footprint "eagle-import:PATCHPOLYGRAPHV1_1005M")
      (libsource (lib "eagle-import") (part "R_OUTLINER0402_OUTLINE"))
    )
    (comp (ref "U11")
      (value "CM1624-08DE")
      (footprint "eagle-import:SON40P135X330X55-17N")
      (fields (field (name "MOUSER_PART_NUMBER") "748-CM1624-08DE"))
      (libsource (lib "eagle-import") (part "CM1624-08DE"))
    )
    (comp (ref "X6")
      (value "MEM2051-00-195-00-A")
      (footprint "eagle-import:MEM20510019500A")
      (fields (field (name "MOUSER_PART_NUMBER") "640-MEM20510019500A"))
      (libsource (lib "eagle-import") (part "MEM2051-00-195-00-A"))
    )
  )
  (nets
    (net (code "1") (name "+3V3_A") (class "Default")
      (node (ref "C14") (pin "1") (pinfunction "1_1") (pintype "passive"))
      (node (ref "C15") (pin "1") (pinfunction "1_1") (pintype "passive"))
      (node (ref "C20") (pin "1") (pinfunction "1_1") (pintype "passive"))
      (node (ref "C21") (pin "1") (pinfunction "1_1") (pintype "passive"))
      (node (ref "C22") (pin "1") (pinfunction "1_1") (pintype "passive"))
      (node (ref "C23") (pin "1") (pinfunction "1_1") (pintype "passive"))
      (node (ref "C24") (pin "1") (pinfunction "1_1") (pintype "passive"))
      (node (ref "C5") (pin "1") (pinfunction "1_1") (pintype "passive"))
      (node (ref "M1") (pin "5") (pinfunction "VDD_5") (pintype "bidirectional"))
      (node (ref "R17") (pin "2") (pinfunction "2_2") (pintype "passive"))
      (node (ref "R29") (pin "2") (pinfunction "2_2") (pintype "passive"))
      (node (ref "TP1") (pin "TP") (pinfunction "TP_TP") (pintype "input"))
      (node (ref "U2") (pin "5") (pinfunction "OUT_5") (pintype "bidirectional"))
      (node (ref "U4") (pin "9") (pinfunction "VDDA/VREF+_9") (pintype "bidirectional"))
      (node (ref "U5") (pin "8") (pinfunction "V+_8") (pintype "power_in"))
      (node (ref "U6") (pin "8") (pinfunction "V+_8") (pintype "power_in"))
      (node (ref "U7") (pin "8") (pinfunction "V+_8") (pintype "power_in"))
    )
    (net (code "2") (name "+3V3_D") (class "Default")
      (node (ref "C11") (pin "1") (pinfunction "1_1") (pintype "passive"))
      (node (ref "C12") (pin "1") (pinfunction "1_1") (pintype "passive"))
      (node (ref "C13") (pin "1") (pinfunction "1_1") (pintype "passive"))
      (node (ref "C3") (pin "1") (pinfunction "1_1") (pintype "passive"))
      (node (ref "C31") (pin "1") (pinfunction "1_1") (pintype "passive"))
      (node (ref "C32") (pin "1") (pinfunction "1_1") (pintype "passive"))
      (node (ref "C33") (pin "1") (pinfunction "1_1") (pintype "passive"))
      (node (ref "C34") (pin "1") (pinfunction "1_1") (pintype "passive"))
      (node (ref "C35") (pin "1") (pinfunction "1_1") (pintype "passive"))
      (node (ref "C36") (pin "1") (pinfunction "1_1") (pintype "passive"))
      (node (ref "D5") (pin "A") (pinfunction "A_A") (pintype "passive"))
      (node (ref "D6") (pin "A") (pinfunction "A_A") (pintype "passive"))
      (node (ref "J3") (pin "2") (pinfunction "2_2") (pintype "passive"))
      (node (ref "J5") (pin "1") (pinfunction "1_1") (pintype "passive"))
      (node (ref "R13") (pin "2") (pinfunction "2_2") (pintype "passive"))
      (node (ref "R14") (pin "2") (pinfunction "2_2") (pintype "passive"))
      (node (ref "R36") (pin "2") (pinfunction "2_2") (pintype "passive"))
      (node (ref "R37") (pin "2") (pinfunction "2_2") (pintype "passive"))
      (node (ref "R39") (pin "2") (pinfunction "2_2") (pintype "passive"))
      (node (ref "U1") (pin "5") (pinfunction "OUT_5") (pintype "bidirectional"))
      (node (ref "U10") (pin "8") (pinfunction "VDD_8") (pintype "bidirectional"))
      (node (ref "U11") (pin "12") (pinfunction "VCC_12") (pintype "bidirectional"))
      (node (ref "U4") (pin "1") (pinfunction "VBAT_1") (pintype "bidirectional"))
      (node (ref "U4") (pin "24") (pinfunction "VDD_1_24") (pintype "bidirectional"))
      (node (ref "U4") (pin "36") (pinfunction "VDDUSB_36") (pintype "bidirectional"))
      (node (ref "U4") (pin "48") (pinfunction "VDD_2_48") (pintype "bidirectional"))
      (node (ref "U9") (pin "2") (pinfunction "RES1_2") (pintype "bidirectional"))
      (node (ref "U9") (pin "3") (pinfunction "RES2_3") (pintype "bidirectional"))
      (node (ref "U9") (pin "5") (pinfunction "VDD_IO_5") (pintype "bidirectional"))
      (node (ref "U9") (pin "8") (pinfunction "VDD_8") (pintype "bidirectional"))
      (node (ref "X6") (pin "P4") (pinfunction "VDD_P4") (pintype "bidirectional"))
    )
    (net (code "3") (name "+5V_A") (class "Default")
      (node (ref "C4") (pin "1") (pinfunction "1_1") (pintype "passive"))
      (node (ref "J1") (pin "1") (pinfunction "1_1") (pintype "passive"))
      (node (ref "U2") (pin "1") (pinfunction "IN_1") (pintype "bidirectional"))
      (node (ref "X2") (pin "1") (pinfunction "1_1") (pintype "passive"))
    )
    (net (code "4") (name "+5V_D") (class "Default")
      (node (ref "C1") (pin "1") (pinfunction "1_1") (pintype "passive"))
      (node (ref "C2") (pin "1") (pinfunction "1_1") (pintype "passive"))
      (node (ref "D2") (pin "A") (pinfunction "A_A") (pintype "passive"))
      (node (ref "F1") (pin "2") (pinfunction "2_2") (pintype "passive"))
      (node (ref "J1") (pin "2") (pinfunction "2_2") (pintype "passive"))
      (node (ref "U1") (pin "1") (pinfunction "IN_1") (pintype "bidirectional"))
      (node (ref "U1") (pin "3") (pinfunction "EN_3") (pintype "bidirectional"))
    )
    (net (code "5") (name "+VBLE") (class "Default")
      (node (ref "D3") (pin "A") (pinfunction "A_A") (pintype "passive"))
      (node (ref "D4") (pin "A") (pinfunction "A_A") (pintype "passive"))
      (node (ref "D7") (pin "A") (pinfunction "A_A") (pintype "passive"))
      (node (ref "J3") (pin "1") (pinfunction "1_1") (pintype "passive"))
      (node (ref "J4") (pin "1") (pinfunction "1_1") (pintype "passive"))
      (node (ref "R4") (pin "2") (pinfunction "2_2") (pintype "passive"))
      (node (ref "R7") (pin "2") (pinfunction "2_2") (pintype "passive"))
      (node (ref "R8") (pin "2") (pinfunction "2_2") (pintype "passive"))
      (node (ref "U3") (pin "15") (pinfunction "VBAT_15") (pintype "bidirectional"))
      (node (ref "U3") (pin "17") (pinfunction "VDD_17") (pintype "bidirectional"))
      (node (ref "U3") (pin "4") (pinfunction "VREF+_4") (pintype "bidirectional"))
      (node (ref "U3") (pin "6") (pinfunction "VDDA_6") (pintype "bidirectional"))
    )
    (net (code "6") (name "ACC_INT1") (class "Default")
      (node (ref "U4") (pin "43") (pinfunction "PB7_43") (pintype "bidirectional"))
      (node (ref "U9") (pin "4") (pinfunction "INT1_4") (pintype "bidirectional"))
    )
    (net (code "7") (name "BOOT0") (class "Default")
      (node (ref "R10") (pin "1") (pinfunction "1_1") (pintype "passive"))
      (node (ref "U4") (pin "44") (pinfunction "PH3-BOOT0_44") (pintype "bidirectional"))
    )
    (net (code "8") (name "BTN") (class "Default")
      (node (ref "R14") (pin "1") (pinfunction "1_1") (pintype "passive"))
      (node (ref "R15") (pin "2") (pinfunction "2_2") (pintype "passive"))
      (node (ref "S4") (pin "1") (pinfunction "P_1") (pintype "passive"))
      (node (ref "U4") (pin "41") (pinfunction "PB5_41") (pintype "bidirectional"))
    )
    (net (code "9") (name "DEV_RDY") (class "Default")
      (node (ref "R4") (pin "1") (pinfunction "1_1") (pintype "passive"))
      (node (ref "U3") (pin "36") (pinfunction "PC6_36") (pintype "bidirectional"))
      (node (ref "U4") (pin "45") (pinfunction "PB8_45") (pintype "bidirectional"))
    )
    (net (code "10") (name "EXT_SEN") (class "Default")
      (node (ref "R35") (pin "1") (pinfunction "1_1") (pintype "passive"))
      (node (ref "U4") (pin "14") (pinfunction "PA4_14") (pintype "bidirectional"))
    )
    (net (code "11") (name "GND") (class "Default")
      (node (ref "C1") (pin "2") (pinfunction "2_2") (pintype "passive"))
      (node (ref "C10") (pin "2") (pinfunction "2_2") (pintype "passive"))
      (node (ref "C11") (pin "2") (pinfunction "2_2") (pintype "passive"))
      (node (ref "C12") (pin "2") (pinfunction "2_2") (pintype "passive"))
      (node (ref "C13") (pin "2") (pinfunction "2_2") (pintype "passive"))
      (node (ref "C14") (pin "2") (pinfunction "2_2") (pintype "passive"))
      (node (ref "C15") (pin "2") (pinfunction "2_2") (pintype "passive"))
      (node (ref "C16") (pin "2") (pinfunction "2_2") (pintype "passive"))
      (node (ref "C17") (pin "2") (pinfunction "2_2") (pintype "passive"))
      (node (ref "C18") (pin "2") (pinfunction "2_2") (pintype "passive"))
      (node (ref "C19") (pin "2") (pinfunction "2_2") (pintype "passive"))
      (node (ref "C2") (pin "2") (pinfunction "2_2") (pintype "passive"))
      (node (ref "C20") (pin "2") (pinfunction "2_2") (pintype "passive"))
      (node (ref "C21") (pin "2") (pinfunction "2_2") (pintype "passive"))
      (node (ref "C22") (pin "2") (pinfunction "2_2") (pintype "passive"))
      (node (ref "C23") (pin "2") (pinfunction "2_2") (pintype "passive"))
      (node (ref "C24") (pin "2") (pinfunction "2_2") (pintype "passive"))
      (node (ref "C25") (pin "2") (pinfunction "2_2") (pintype "passive"))
      (node (ref "C3") (pin "2") (pinfunction "2_2") (pintype "passive"))
      (node (ref "C31") (pin "2") (pinfunction "2_2") (pintype "passive"))
      (node (ref "C32") (pin "2") (pinfunction "2_2") (pintype "passive"))
      (node (ref "C33") (pin "2") (pinfunction "2_2") (pintype "passive"))
      (node (ref "C34") (pin "2") (pinfunction "2_2") (pintype "passive"))
      (node (ref "C35") (pin "2") (pinfunction "2_2") (pintype "passive"))
      (node (ref "C36") (pin "2") (pinfunction "2_2") (pintype "passive"))
      (node (ref "C4") (pin "2") (pinfunction "2_2") (pintype "passive"))
      (node (ref "C5") (pin "2") (pinfunction "2_2") (pintype "passive"))
      (node (ref "C6") (pin "2") (pinfunction "2_2") (pintype "passive"))
      (node (ref "C7") (pin "2") (pinfunction "2_2") (pintype "passive"))
      (node (ref "C8") (pin "2") (pinfunction "2_2") (pintype "passive"))
      (node (ref "C9") (pin "2") (pinfunction "2_2") (pintype "passive"))
      (node (ref "D1") (pin "2") (pinfunction "A_2") (pintype "bidirectional"))
      (node (ref "J2") (pin "1") (pinfunction "1_1") (pintype "passive"))
      (node (ref "J4") (pin "3") (pinfunction "3_3") (pintype "passive"))
      (node (ref "J5") (pin "3") (pinfunction "3_3") (pintype "passive"))
      (node (ref "M1") (pin "2") (pinfunction "GND2_2") (pintype "bidirectional"))
      (node (ref "M1") (pin "3") (pinfunction "GND3_3") (pintype "bidirectional"))
      (node (ref "M1") (pin "4") (pinfunction "GND1_4") (pintype "bidirectional"))
      (node (ref "R18") (pin "1") (pinfunction "1_1") (pintype "passive"))
      (node (ref "R2") (pin "1") (pinfunction "1_1") (pintype "passive"))
      (node (ref "R28") (pin "1") (pinfunction "1_1") (pintype "passive"))
      (node (ref "R30") (pin "1") (pinfunction "1_1") (pintype "passive"))
      (node (ref "R34") (pin "1") (pinfunction "1_1") (pintype "passive"))
      (node (ref "S1") (pin "2") (pinfunction "S_2") (pintype "passive"))
      (node (ref "S2") (pin "2") (pinfunction "S_2") (pintype "passive"))
      (node (ref "S3") (pin "2") (pinfunction "S_2") (pintype "passive"))
      (node (ref "S4") (pin "2") (pinfunction "S_2") (pintype "passive"))
      (node (ref "U1") (pin "2") (pinfunction "GND_2") (pintype "power_in"))
      (node (ref "U10") (pin "4") (pinfunction "GND_4") (pintype "bidirectional"))
      (node (ref "U10") (pin "5") (pinfunction "A2_5") (pintype "bidirectional"))
      (node (ref "U10") (pin "6") (pinfunction "A1_6") (pintype "bidirectional"))
      (node (ref "U10") (pin "7") (pinfunction "A0_7") (pintype "bidirectional"))
      (node (ref "U10") (pin "9") (pinfunction "EP_9") (pintype "bidirectional"))
      (node (ref "U11") (pin "17") (pinfunction "EP_17") (pintype "bidirectional"))
      (node (ref "U2") (pin "2") (pinfunction "GND_2") (pintype "power_in"))
      (node (ref "U3") (pin "16") (pinfunction "VSS_2_16") (pintype "bidirectional"))
      (node (ref "U3") (pin "31") (pinfunction "VSS_3_31") (pintype "bidirectional"))
      (node (ref "U3") (pin "32") (pinfunction "VDDUSB_32") (pintype "bidirectional"))
      (node (ref "U3") (pin "5") (pinfunction "VSS_1_5") (pintype "bidirectional"))
      (node (ref "U3") (pin "57") (pinfunction "VSS_4_57") (pintype "bidirectional"))
      (node (ref "U3") (pin "58") (pinfunction "ANT_IN_58") (pintype "bidirectional"))
      (node (ref "U3") (pin "59") (pinfunction "RF_OUT_59") (pintype "bidirectional"))
      (node (ref "U3") (pin "60") (pinfunction "VSS_5_60") (pintype "bidirectional"))
      (node (ref "U3") (pin "72") (pinfunction "PE3_72") (pintype "bidirectional"))
      (node (ref "U3") (pin "73") (pinfunction "PD4_73") (pintype "bidirectional"))
      (node (ref "U3") (pin "83") (pinfunction "PC8_83") (pintype "bidirectional"))
      (node (ref "U3") (pin "84") (pinfunction "VSS_6_84") (pintype "bidirectional"))
      (node (ref "U3") (pin "86") (pinfunction "VSS_7_86") (pintype "bidirectional"))
      (node (ref "U4") (pin "23") (pinfunction "VSS_1_23") (pintype "bidirectional"))
      (node (ref "U4") (pin "35") (pinfunction "VSS_2_35") (pintype "bidirectional"))
      (node (ref "U4") (pin "47") (pinfunction "VSS_3_47") (pintype "bidirectional"))
      (node (ref "U4") (pin "49") (pinfunction "EP_49") (pintype "bidirectional"))
      (node (ref "U4") (pin "8") (pinfunction "VSSA/VREF-_8") (pintype "bidirectional"))
      (node (ref "U5") (pin "4") (pinfunction "V-_4") (pintype "power_in"))
      (node (ref "U6") (pin "4") (pinfunction "V-_4") (pintype "power_in"))
      (node (ref "U7") (pin "4") (pinfunction "V-_4") (pintype "power_in"))
      (node (ref "U9") (pin "6") (pinfunction "GND1_6") (pintype "bidirectional"))
      (node (ref "U9") (pin "7") (pinfunction "GND2_7") (pintype "bidirectional"))
      (node (ref "X1") (pin "2") (pinfunction "2_2") (pintype "passive"))
      (node (ref "X2") (pin "2") (pinfunction "1_2") (pintype "passive"))
      (node (ref "X3") (pin "2") (pinfunction "1_2") (pintype "passive"))
      (node (ref "X4") (pin "2") (pinfunction "1_2") (pintype "passive"))
      (node (ref "X5") (pin "2") (pinfunction "GND_1_2") (pintype "bidirectional"))
      (node (ref "X5") (pin "3") (pinfunction "GND_2_3") (pintype "bidirectional"))
      (node (ref "X6") (pin "MP1") (pinfunction "MP1_MP1") (pintype "bidirectional"))
      (node (ref "X6") (pin "MP2") (pinfunction "MP2_MP2") (pintype "bidirectional"))
      (node (ref "X6") (pin "MP3") (pinfunction "MP3_MP3") (pintype "bidirectional"))
      (node (ref "X6") (pin "MP4") (pinfunction "MP4_MP4") (pintype "bidirectional"))
      (node (ref "X6") (pin "P6") (pinfunction "VSS_P6") (pintype "bidirectional"))
      (node (ref "Y1") (pin "2") (pinfunction "GND_1_2") (pintype "bidirectional"))
      (node (ref "Y1") (pin "4") (pinfunction "GND_2_4") (pintype "bidirectional"))
    )
    (net (code "12") (name "I2C_SCL") (class "Default")
      (node (ref "R37") (pin "1") (pinfunction "1_1") (pintype "passive"))
      (node (ref "U10") (pin "2") (pinfunction "SCL_2") (pintype "bidirectional"))
      (node (ref "U4") (pin "21") (pinfunction "PB10_21") (pintype "bidirectional"))
    )
    (net (code "13") (name "I2C_SDA") (class "Default")
      (node (ref "R36") (pin "1") (pinfunction "1_1") (pintype "passive"))
      (node (ref "U10") (pin "1") (pinfunction "SDA_1") (pintype "bidirectional"))
      (node (ref "U4") (pin "22") (pinfunction "PB11_22") (pintype "bidirectional"))
    )
    (net (code "14") (name "LED1") (class "Default")
      (node (ref "R11") (pin "1") (pinfunction "1_1") (pintype "passive"))
      (node (ref "U4") (pin "33") (pinfunction "PA12_33") (pintype "bidirectional"))
    )
    (net (code "15") (name "LED2") (class "Default")
      (node (ref "R12") (pin "1") (pinfunction "1_1") (pintype "passive"))
      (node (ref "U4") (pin "32") (pinfunction "PA11_32") (pintype "bidirectional"))
    )
    (net (code "16") (name "MCU1_NRST") (class "Default")
      (node (ref "C9") (pin "1") (pinfunction "1_1") (pintype "passive"))
      (node (ref "R7") (pin "1") (pinfunction "1_1") (pintype "passive"))
      (node (ref "S1") (pin "1") (pinfunction "P_1") (pintype "passive"))
      (node (ref "U3") (pin "10") (pinfunction "NRST_10") (pintype "bidirectional"))
      (node (ref "X3") (pin "4") (pinfunction "1_4") (pintype "passive"))
    )
    (net (code "17") (name "MCU1_SWCLK") (class "Default")
      (node (ref "U3") (pin "26") (pinfunction "PA14_26") (pintype "bidirectional"))
      (node (ref "X3") (pin "1") (pinfunction "1_1") (pintype "passive"))
    )
    (net (code "18") (name "MCU1_SWDIO") (class "Default")
      (node (ref "U3") (pin "25") (pinfunction "PA13_25") (pintype "bidirectional"))
      (node (ref "X3") (pin "3") (pinfunction "1_3") (pintype "passive"))
    )
    (net (code "19") (name "MCU2_NRST") (class "Default")
      (node (ref "C16") (pin "1") (pinfunction "1_1") (pintype "passive"))
      (node (ref "R13") (pin "1") (pinfunction "1_1") (pintype "passive"))
      (node (ref "S3") (pin "1") (pinfunction "P_1") (pintype "passive"))
      (node (ref "U4") (pin "7") (pinfunction "NRST_7") (pintype "bidirectional"))
      (node (ref "X4") (pin "4") (pinfunction "1_4") (pintype "passive"))
    )
    (net (code "20") (name "MCU2_SWCLK") (class "Default")
      (node (ref "U4") (pin "37") (pinfunction "PA14_37") (pintype "bidirectional"))
      (node (ref "X4") (pin "1") (pinfunction "1_1") (pintype "passive"))
    )
    (net (code "21") (name "MCU2_SWDIO") (class "Default")
      (node (ref "U4") (pin "34") (pinfunction "PA13_34") (pintype "bidirectional"))
      (node (ref "X4") (pin "3") (pinfunction "1_3") (pintype "passive"))
    )
    (net (code "22") (name "MIC_OUT") (class "Default")
      (node (ref "R26") (pin "1") (pinfunction "1_1") (pintype "passive"))
      (node (ref "U4") (pin "13") (pinfunction "PA3_13") (pintype "bidirectional"))
    )
    (net (code "23") (name "Net-(C10-Pad1)") (class "Default")
      (node (ref "C10") (pin "1") (pinfunction "1_1") (pintype "passive"))
      (node (ref "R9") (pin "1") (pinfunction "1_1") (pintype "passive"))
    )
    (net (code "24") (name "Net-(C17-Pad1)") (class "Default")
      (node (ref "C17") (pin "1") (pinfunction "1_1") (pintype "passive"))
      (node (ref "R15") (pin "1") (pinfunction "1_1") (pintype "passive"))
    )
    (net (code "25") (name "Net-(C28-Pad2)") (class "Default")
      (node (ref "C28") (pin "2") (pinfunction "2_2") (pintype "passive"))
      (node (ref "R22") (pin "2") (pinfunction "2_2") (pintype "passive"))
      (node (ref "R23") (pin "1") (pinfunction "1_1") (pintype "passive"))
    )
    (net (code "26") (name "Net-(C30-Pad2)") (class "Default")
      (node (ref "C30") (pin "2") (pinfunction "2_2") (pintype "passive"))
      (node (ref "R24") (pin "1") (pinfunction "1_1") (pintype "passive"))
      (node (ref "R25") (pin "2") (pinfunction "2_2") (pintype "passive"))
    )
    (net (code "27") (name "Net-(D1-K)") (class "Default")
      (node (ref "D1") (pin "1") (pinfunction "K_1") (pintype "bidirectional"))
      (node (ref "F1") (pin "1") (pinfunction "1_1") (pintype "passive"))
      (node (ref "X1") (pin "1") (pinfunction "1_1") (pintype "passive"))
    )
    (net (code "28") (name "Net-(D2-PadC)") (class "Default")
      (node (ref "D2") (pin "C") (pinfunction "C_C") (pintype "passive"))
      (node (ref "R1") (pin "2") (pinfunction "2_2") (pintype "passive"))
    )
    (net (code "29") (name "Net-(D3-PadC)") (class "Default")
      (node (ref "D3") (pin "C") (pinfunction "C_C") (pintype "passive"))
      (node (ref "R5") (pin "2") (pinfunction "2_2") (pintype "passive"))
    )
    (net (code "30") (name "Net-(D4-PadC)") (class "Default")
      (node (ref "D4") (pin "C") (pinfunction "C_C") (pintype "passive"))
      (node (ref "R6") (pin "2") (pinfunction "2_2") (pintype "passive"))
    )
    (net (code "31") (name "Net-(D5-PadC)") (class "Default")
      (node (ref "D5") (pin "C") (pinfunction "C_C") (pintype "passive"))
      (node (ref "R11") (pin "2") (pinfunction "2_2") (pintype "passive"))
    )
    (net (code "32") (name "Net-(D6-PadC)") (class "Default")
      (node (ref "D6") (pin "C") (pinfunction "C_C") (pintype "passive"))
      (node (ref "R12") (pin "2") (pinfunction "2_2") (pintype "passive"))
    )
    (net (code "33") (name "Net-(D7-PadC)") (class "Default")
      (node (ref "D7") (pin "C") (pinfunction "C_C") (pintype "passive"))
      (node (ref "R38") (pin "2") (pinfunction "2_2") (pintype "passive"))
    )
    (net (code "34") (name "Net-(J2-Pad2)") (class "Default")
      (node (ref "J2") (pin "2") (pinfunction "2_2") (pintype "passive"))
      (node (ref "R1") (pin "1") (pinfunction "1_1") (pintype "passive"))
    )
    (net (code "35") (name "Net-(J4-Pad2)") (class "Default")
      (node (ref "J4") (pin "2") (pinfunction "2_2") (pintype "passive"))
      (node (ref "R3") (pin "2") (pinfunction "2_2") (pintype "passive"))
    )
    (net (code "36") (name "Net-(J5-Pad2)") (class "Default")
      (node (ref "J5") (pin "2") (pinfunction "2_2") (pintype "passive"))
      (node (ref "R10") (pin "2") (pinfunction "2_2") (pintype "passive"))
    )
    (net (code "37") (name "Net-(M1-OUT)") (class "Default")
      (node (ref "C26") (pin "1") (pinfunction "1_1") (pintype "passive"))
      (node (ref "M1") (pin "1") (pinfunction "OUT_1") (pintype "bidirectional"))
      (node (ref "TP2") (pin "TP") (pinfunction "TP_TP") (pintype "input"))
    )
    (net (code "38") (name "Net-(R27-Pad2)") (class "Default")
      (node (ref "R27") (pin "2") (pinfunction "2_2") (pintype "passive"))
      (node (ref "R28") (pin "2") (pinfunction "2_2") (pintype "passive"))
      (node (ref "R31") (pin "1") (pinfunction "1_1") (pintype "passive"))
    )
    (net (code "39") (name "Net-(U3-PA10)") (class "Default")
      (node (ref "R5") (pin "1") (pinfunction "1_1") (pintype "passive"))
      (node (ref "U3") (pin "28") (pinfunction "PA10_28") (pintype "bidirectional"))
    )
    (net (code "40") (name "Net-(U3-PA11)") (class "Default")
      (node (ref "R6") (pin "1") (pinfunction "1_1") (pintype "passive"))
      (node (ref "U3") (pin "30") (pinfunction "PA11_30") (pintype "bidirectional"))
    )
    (net (code "41") (name "Net-(U3-PA12)") (class "Default")
      (node (ref "PA12") (pin "TP") (pinfunction "TP_TP") (pintype "input"))
      (node (ref "U3") (pin "29") (pinfunction "PA12_29") (pintype "bidirectional"))
    )
    (net (code "42") (name "Net-(U3-PB5)") (class "Default")
      (node (ref "PB5") (pin "TP") (pinfunction "TP_TP") (pintype "input"))
      (node (ref "U3") (pin "19") (pinfunction "PB5_19") (pintype "bidirectional"))
    )
    (net (code "43") (name "Net-(U3-PB10)") (class "Default")
      (node (ref "C8") (pin "1") (pinfunction "1_1") (pintype "passive"))
      (node (ref "U3") (pin "47") (pinfunction "PB10_47") (pintype "bidirectional"))
    )
    (net (code "44") (name "Net-(U3-PB11)") (class "Default")
      (node (ref "C7") (pin "1") (pinfunction "1_1") (pintype "passive"))
      (node (ref "U3") (pin "46") (pinfunction "PB11_46") (pintype "bidirectional"))
    )
    (net (code "45") (name "Net-(U3-PB12)") (class "Default")
      (node (ref "PB12") (pin "TP") (pinfunction "TP_TP") (pintype "input"))
      (node (ref "U3") (pin "41") (pinfunction "PB12_41") (pintype "bidirectional"))
    )
    (net (code "46") (name "Net-(U3-PC2)") (class "Default")
      (node (ref "R38") (pin "1") (pinfunction "1_1") (pintype "passive"))
      (node (ref "U3") (pin "8") (pinfunction "PC2_8") (pintype "bidirectional"))
    )
    (net (code "47") (name "Net-(U3-PC5)") (class "Default")
      (node (ref "C6") (pin "1") (pinfunction "1_1") (pintype "passive"))
      (node (ref "U3") (pin "45") (pinfunction "PC5_45") (pintype "bidirectional"))
    )
    (net (code "48") (name "Net-(U3-PC12)") (class "Default")
      (node (ref "PC12") (pin "TP") (pinfunction "TP_TP") (pintype "input"))
      (node (ref "U3") (pin "24") (pinfunction "PC12_24") (pintype "bidirectional"))
    )
    (net (code "49") (name "Net-(U3-PD1)") (class "Default")
      (node (ref "PD1") (pin "TP") (pinfunction "TP_TP") (pintype "input"))
      (node (ref "U3") (pin "34") (pinfunction "PD1_34") (pintype "bidirectional"))
    )
    (net (code "50") (name "Net-(U3-PH3-BOOT0)") (class "Default")
      (node (ref "R3") (pin "1") (pinfunction "1_1") (pintype "passive"))
      (node (ref "U3") (pin "13") (pinfunction "PH3-BOOT0_13") (pintype "bidirectional"))
    )
    (net (code "51") (name "Net-(U5A-+IN)") (class "Default")
      (node (ref "C25") (pin "1") (pinfunction "1_1") (pintype "passive"))
      (node (ref "R17") (pin "1") (pinfunction "1_1") (pintype "passive"))
      (node (ref "R18") (pin "2") (pinfunction "2_2") (pintype "passive"))
      (node (ref "U5") (pin "3") (pinfunction "+IN_3") (pintype "input"))
    )
    (net (code "52") (name "Net-(U5B-+IN)") (class "Default")
      (node (ref "C26") (pin "2") (pinfunction "2_2") (pintype "passive"))
      (node (ref "R19") (pin "1") (pinfunction "1_1") (pintype "passive"))
      (node (ref "U5") (pin "5") (pinfunction "+IN_5") (pintype "input"))
    )
    (net (code "53") (name "Net-(U5B--IN)") (class "Default")
      (node (ref "R20") (pin "1") (pinfunction "1_1") (pintype "passive"))
      (node (ref "R21") (pin "2") (pinfunction "2_2") (pintype "passive"))
      (node (ref "U5") (pin "6") (pinfunction "-IN_6") (pintype "input"))
    )
    (net (code "54") (name "Net-(U5B-OUT)") (class "Default")
      (node (ref "R21") (pin "1") (pinfunction "1_1") (pintype "passive"))
      (node (ref "R22") (pin "1") (pinfunction "1_1") (pintype "passive"))
      (node (ref "U5") (pin "7") (pinfunction "OUT_7") (pintype "output"))
    )
    (net (code "55") (name "Net-(U6A-+IN)") (class "Default")
      (node (ref "C27") (pin "2") (pinfunction "2_2") (pintype "passive"))
      (node (ref "R23") (pin "2") (pinfunction "2_2") (pintype "passive"))
      (node (ref "U6") (pin "3") (pinfunction "+IN_3") (pintype "input"))
    )
    (net (code "56") (name "Net-(U6A--IN)") (class "Default")
      (node (ref "C28") (pin "1") (pinfunction "1_1") (pintype "passive"))
      (node (ref "R24") (pin "2") (pinfunction "2_2") (pintype "passive"))
      (node (ref "U6") (pin "1") (pinfunction "OUT_1") (pintype "output"))
      (node (ref "U6") (pin "2") (pinfunction "-IN_2") (pintype "input"))
    )
    (net (code "57") (name "Net-(U6B-+IN)") (class "Default")
      (node (ref "C29") (pin "2") (pinfunction "2_2") (pintype "passive"))
      (node (ref "R25") (pin "1") (pinfunction "1_1") (pintype "passive"))
      (node (ref "U6") (pin "5") (pinfunction "+IN_5") (pintype "input"))
    )
    (net (code "58") (name "Net-(U6B--IN)") (class "Default")
      (node (ref "C30") (pin "1") (pinfunction "1_1") (pintype "passive"))
      (node (ref "R26") (pin "2") (pinfunction "2_2") (pintype "passive"))
      (node (ref "U6") (pin "6") (pinfunction "-IN_6") (pintype "input"))
      (node (ref "U6") (pin "7") (pinfunction "OUT_7") (pintype "output"))
    )
    (net (code "59") (name "Net-(U7A-+IN)") (class "Default")
      (node (ref "R29") (pin "1") (pinfunction "1_1") (pintype "passive"))
      (node (ref "R30") (pin "2") (pinfunction "2_2") (pintype "passive"))
      (node (ref "U7") (pin "3") (pinfunction "+IN_3") (pintype "input"))
    )
    (net (code "60") (name "Net-(U7B-+IN)") (class "Default")
      (node (ref "R31") (pin "2") (pinfunction "2_2") (pintype "passive"))
      (node (ref "R32") (pin "2") (pinfunction "2_2") (pintype "passive"))
      (node (ref "U7") (pin "5") (pinfunction "+IN_5") (pintype "input"))
    )
    (net (code "61") (name "Net-(U7B--IN)") (class "Default")
      (node (ref "R33") (pin "1") (pinfunction "1_1") (pintype "passive"))
      (node (ref "R34") (pin "2") (pinfunction "2_2") (pintype "passive"))
      (node (ref "U7") (pin "6") (pinfunction "-IN_6") (pintype "input"))
    )
    (net (code "62") (name "Net-(U7B-OUT)") (class "Default")
      (node (ref "R33") (pin "2") (pinfunction "2_2") (pintype "passive"))
      (node (ref "R35") (pin "2") (pinfunction "2_2") (pintype "passive"))
      (node (ref "U7") (pin "7") (pinfunction "OUT_7") (pintype "output"))
    )
    (net (code "63") (name "Net-(U11-SDCLK)") (class "Default")
      (node (ref "U11") (pin "3") (pinfunction "SDCLK_3") (pintype "bidirectional"))
      (node (ref "X6") (pin "P5") (pinfunction "CLK_P5") (pintype "bidirectional"))
    )
    (net (code "64") (name "Net-(U11-SDCMD)") (class "Default")
      (node (ref "U11") (pin "6") (pinfunction "SDCMD_6") (pintype "bidirectional"))
      (node (ref "X6") (pin "P3") (pinfunction "CMD_P3") (pintype "bidirectional"))
    )
    (net (code "65") (name "Net-(U11-SDDATA0)") (class "Default")
      (node (ref "U11") (pin "2") (pinfunction "SDDATA0_2") (pintype "bidirectional"))
      (node (ref "X6") (pin "P7") (pinfunction "DAT0_P7") (pintype "bidirectional"))
    )
    (net (code "66") (name "Net-(U11-SDDATA1)") (class "Default")
      (node (ref "U11") (pin "1") (pinfunction "SDDATA1_1") (pintype "bidirectional"))
      (node (ref "X6") (pin "P8") (pinfunction "DAT1_P8") (pintype "bidirectional"))
    )
    (net (code "67") (name "Net-(U11-SDDATA2)") (class "Default")
      (node (ref "U11") (pin "8") (pinfunction "SDDATA2_8") (pintype "bidirectional"))
      (node (ref "X6") (pin "P1") (pinfunction "DAT2_P1") (pintype "bidirectional"))
    )
    (net (code "68") (name "Net-(U11-SDDATA3)") (class "Default")
      (node (ref "U11") (pin "7") (pinfunction "SDDATA3_7") (pintype "bidirectional"))
      (node (ref "X6") (pin "P2") (pinfunction "CD/DAT3_P2") (pintype "bidirectional"))
    )
    (net (code "69") (name "Net-(X5-SIG)") (class "Default")
      (node (ref "R27") (pin "1") (pinfunction "1_1") (pintype "passive"))
      (node (ref "X5") (pin "1") (pinfunction "SIG_1") (pintype "bidirectional"))
    )
    (net (code "70") (name "Net-(Y1-OSC_2)") (class "Default")
      (node (ref "C19") (pin "1") (pinfunction "1_1") (pintype "passive"))
      (node (ref "R16") (pin "1") (pinfunction "1_1") (pintype "passive"))
      (node (ref "Y1") (pin "3") (pinfunction "OSC_2_3") (pintype "bidirectional"))
    )
    (net (code "71") (name "OSC_IN") (class "Default")
      (node (ref "C18") (pin "1") (pinfunction "1_1") (pintype "passive"))
      (node (ref "U4") (pin "5") (pinfunction "PH0-OSC_IN_5") (pintype "bidirectional"))
      (node (ref "Y1") (pin "1") (pinfunction "OSC_1_1") (pintype "bidirectional"))
    )
    (net (code "72") (name "OSC_OUT") (class "Default")
      (node (ref "R16") (pin "2") (pinfunction "2_2") (pintype "passive"))
      (node (ref "U4") (pin "6") (pinfunction "PH1-OSC_OUT_6") (pintype "bidirectional"))
    )
    (net (code "73") (name "PD0") (class "Default")
      (node (ref "R8") (pin "1") (pinfunction "1_1") (pintype "passive"))
      (node (ref "R9") (pin "2") (pinfunction "2_2") (pintype "passive"))
      (node (ref "S2") (pin "1") (pinfunction "P_1") (pintype "passive"))
      (node (ref "U3") (pin "33") (pinfunction "PD0_33") (pintype "bidirectional"))
    )
    (net (code "74") (name "SD_CD") (class "Default")
      (node (ref "R39") (pin "1") (pinfunction "1_1") (pintype "passive"))
      (node (ref "U4") (pin "26") (pinfunction "PB13_26") (pintype "bidirectional"))
      (node (ref "X6") (pin "CD") (pinfunction "CD_CD") (pintype "bidirectional"))
    )
    (net (code "75") (name "SD_CK") (class "Default")
      (node (ref "U11") (pin "14") (pinfunction "CLK_14") (pintype "bidirectional"))
      (node (ref "U4") (pin "25") (pinfunction "PB12_25") (pintype "bidirectional"))
    )
    (net (code "76") (name "SD_CMD") (class "Default")
      (node (ref "U11") (pin "11") (pinfunction "CMD_11") (pintype "bidirectional"))
      (node (ref "U4") (pin "11") (pinfunction "PA1_11") (pintype "bidirectional"))
    )
    (net (code "77") (name "SD_D0") (class "Default")
      (node (ref "U11") (pin "15") (pinfunction "DATA0_15") (pintype "bidirectional"))
      (node (ref "U4") (pin "27") (pinfunction "PB14_27") (pintype "bidirectional"))
    )
    (net (code "78") (name "SD_D1") (class "Default")
      (node (ref "U11") (pin "16") (pinfunction "DATA1_16") (pintype "bidirectional"))
      (node (ref "U4") (pin "28") (pinfunction "PB15_28") (pintype "bidirectional"))
    )
    (net (code "79") (name "SD_D2") (class "Default")
      (node (ref "U11") (pin "10") (pinfunction "DATA3_10") (pintype "bidirectional"))
      (node (ref "U4") (pin "39") (pinfunction "PB3_39") (pintype "bidirectional"))
    )
    (net (code "80") (name "SD_D3") (class "Default")
      (node (ref "U11") (pin "9") (pinfunction "DATA2_9") (pintype "bidirectional"))
      (node (ref "U4") (pin "40") (pinfunction "PB4_40") (pintype "bidirectional"))
    )
    (net (code "81") (name "SENSOR_EN") (class "Default")
      (node (ref "R2") (pin "2") (pinfunction "2_2") (pintype "passive"))
      (node (ref "U2") (pin "3") (pinfunction "EN_3") (pintype "bidirectional"))
      (node (ref "U4") (pin "20") (pinfunction "PB2_20") (pintype "bidirectional"))
    )
    (net (code "82") (name "SPI_CS") (class "Default")
      (node (ref "U4") (pin "18") (pinfunction "PB0_18") (pintype "bidirectional"))
      (node (ref "U9") (pin "12") (pinfunction "CS_12") (pintype "bidirectional"))
    )
    (net (code "83") (name "SPI_MISO") (class "Default")
      (node (ref "U4") (pin "16") (pinfunction "PA6_16") (pintype "bidirectional"))
      (node (ref "U9") (pin "1") (pinfunction "SDO/SA0_1") (pintype "bidirectional"))
    )
    (net (code "84") (name "SPI_MOSI") (class "Default")
      (node (ref "U4") (pin "17") (pinfunction "PA7_17") (pintype "bidirectional"))
      (node (ref "U9") (pin "14") (pinfunction "SDI/SDA_14") (pintype "bidirectional"))
    )
    (net (code "85") (name "SPI_SCK") (class "Default")
      (node (ref "U4") (pin "15") (pinfunction "PA5_15") (pintype "bidirectional"))
      (node (ref "U9") (pin "13") (pinfunction "SPC/SCL_13") (pintype "bidirectional"))
    )
    (net (code "86") (name "UART_RX") (class "Default")
      (node (ref "RX") (pin "TP") (pinfunction "TP_TP") (pintype "input"))
      (node (ref "U3") (pin "39") (pinfunction "PB6_39") (pintype "bidirectional"))
      (node (ref "U4") (pin "31") (pinfunction "PA10_31") (pintype "bidirectional"))
    )
    (net (code "87") (name "UART_TX") (class "Default")
      (node (ref "TX") (pin "TP") (pinfunction "TP_TP") (pintype "input"))
      (node (ref "U3") (pin "18") (pinfunction "PB7_18") (pintype "bidirectional"))
      (node (ref "U4") (pin "30") (pinfunction "PA9_30") (pintype "bidirectional"))
    )
    (net (code "88") (name "VREF1") (class "Default")
      (node (ref "C27") (pin "1") (pinfunction "1_1") (pintype "passive"))
      (node (ref "C29") (pin "1") (pinfunction "1_1") (pintype "passive"))
      (node (ref "R19") (pin "2") (pinfunction "2_2") (pintype "passive"))
      (node (ref "R20") (pin "2") (pinfunction "2_2") (pintype "passive"))
      (node (ref "U4") (pin "10") (pinfunction "PA0_10") (pintype "bidirectional"))
      (node (ref "U5") (pin "1") (pinfunction "OUT_1") (pintype "output"))
      (node (ref "U5") (pin "2") (pinfunction "-IN_2") (pintype "input"))
    )
    (net (code "89") (name "VREF2") (class "Default")
      (node (ref "R32") (pin "1") (pinfunction "1_1") (pintype "passive"))
      (node (ref "U4") (pin "12") (pinfunction "PA2_12") (pintype "bidirectional"))
      (node (ref "U7") (pin "1") (pinfunction "OUT_1") (pintype "output"))
      (node (ref "U7") (pin "2") (pinfunction "-IN_2") (pintype "input"))
    )
    (net (code "90") (name "unconnected-(U1-NC-Pad4)") (class "Default")
      (node (ref "U1") (pin "4") (pinfunction "NC_4") (pintype "no_connect"))
    )
    (net (code "91") (name "unconnected-(U2-NC-Pad4)") (class "Default")
      (node (ref "U2") (pin "4") (pinfunction "NC_4") (pintype "no_connect"))
    )
    (net (code "92") (name "unconnected-(U3-ANT_NC-Pad85)") (class "Default")
      (node (ref "U3") (pin "85") (pinfunction "ANT_NC_85") (pintype "no_connect"))
    )
    (net (code "93") (name "unconnected-(U3-PA0-Pad3)") (class "Default")
      (node (ref "U3") (pin "3") (pinfunction "PA0_3") (pintype "bidirectional"))
    )
    (net (code "94") (name "unconnected-(U3-PA1-Pad2)") (class "Default")
      (node (ref "U3") (pin "2") (pinfunction "PA1_2") (pintype "bidirectional"))
    )
    (net (code "95") (name "unconnected-(U3-PA2-Pad1)") (class "Default")
      (node (ref "U3") (pin "1") (pinfunction "PA2_1") (pintype "bidirectional"))
    )
    (net (code "96") (name "unconnected-(U3-PA3-Pad56)") (class "Default")
      (node (ref "U3") (pin "56") (pinfunction "PA3_56") (pintype "bidirectional"))
    )
    (net (code "97") (name "unconnected-(U3-PA4-Pad55)") (class "Default")
      (node (ref "U3") (pin "55") (pinfunction "PA4_55") (pintype "bidirectional"))
    )
    (net (code "98") (name "unconnected-(U3-PA5-Pad54)") (class "Default")
      (node (ref "U3") (pin "54") (pinfunction "PA5_54") (pintype "bidirectional"))
    )
    (net (code "99") (name "unconnected-(U3-PA6-Pad53)") (class "Default")
      (node (ref "U3") (pin "53") (pinfunction "PA6_53") (pintype "bidirectional"))
    )
    (net (code "100") (name "unconnected-(U3-PA7-Pad52)") (class "Default")
      (node (ref "U3") (pin "52") (pinfunction "PA7_52") (pintype "bidirectional"))
    )
    (net (code "101") (name "unconnected-(U3-PA8-Pad50)") (class "Default")
      (node (ref "U3") (pin "50") (pinfunction "PA8_50") (pintype "bidirectional"))
    )
    (net (code "102") (name "unconnected-(U3-PA9-Pad51)") (class "Default")
      (node (ref "U3") (pin "51") (pinfunction "PA9_51") (pintype "bidirectional"))
    )
    (net (code "103") (name "unconnected-(U3-PA15-Pad27)") (class "Default")
      (node (ref "U3") (pin "27") (pinfunction "PA15_27") (pintype "bidirectional"))
    )
    (net (code "104") (name "unconnected-(U3-PB0-Pad43)") (class "Default")
      (node (ref "U3") (pin "43") (pinfunction "PB0_43") (pintype "no_connect"))
    )
    (net (code "105") (name "unconnected-(U3-PB1-Pad44)") (class "Default")
      (node (ref "U3") (pin "44") (pinfunction "PB1_44") (pintype "no_connect"))
    )
    (net (code "106") (name "unconnected-(U3-PB2-Pad48)") (class "Default")
      (node (ref "U3") (pin "48") (pinfunction "PB2_48") (pintype "bidirectional"))
    )
    (net (code "107") (name "unconnected-(U3-PB3-Pad21)") (class "Default")
      (node (ref "U3") (pin "21") (pinfunction "PB3_21") (pintype "bidirectional"))
    )
    (net (code "108") (name "unconnected-(U3-PB4-Pad20)") (class "Default")
      (node (ref "U3") (pin "20") (pinfunction "PB4_20") (pintype "bidirectional"))
    )
    (net (code "109") (name "unconnected-(U3-PB8-Pad14)") (class "Default")
      (node (ref "U3") (pin "14") (pinfunction "PB8_14") (pintype "bidirectional"))
    )
    (net (code "110") (name "unconnected-(U3-PB9-Pad11)") (class "Default")
      (node (ref "U3") (pin "11") (pinfunction "PB9_11") (pintype "bidirectional"))
    )
    (net (code "111") (name "unconnected-(U3-PB13-Pad35)") (class "Default")
      (node (ref "U3") (pin "35") (pinfunction "PB13_35") (pintype "bidirectional"))
    )
    (net (code "112") (name "unconnected-(U3-PB14-Pad37)") (class "Default")
      (node (ref "U3") (pin "37") (pinfunction "PB14_37") (pintype "bidirectional"))
    )
    (net (code "113") (name "unconnected-(U3-PB15-Pad38)") (class "Default")
      (node (ref "U3") (pin "38") (pinfunction "PB15_38") (pintype "bidirectional"))
    )
    (net (code "114") (name "unconnected-(U3-PC0-Pad12)") (class "Default")
      (node (ref "U3") (pin "12") (pinfunction "PC0_12") (pintype "bidirectional"))
    )
    (net (code "115") (name "unconnected-(U3-PC1-Pad9)") (class "Default")
      (node (ref "U3") (pin "9") (pinfunction "PC1_9") (pintype "bidirectional"))
    )
    (net (code "116") (name "unconnected-(U3-PC3-Pad7)") (class "Default")
      (node (ref "U3") (pin "7") (pinfunction "PC3_7") (pintype "bidirectional"))
    )
    (net (code "117") (name "unconnected-(U3-PC4-Pad49)") (class "Default")
      (node (ref "U3") (pin "49") (pinfunction "PC4_49") (pintype "bidirectional"))
    )
    (net (code "118") (name "unconnected-(U3-PC7-Pad71)") (class "Default")
      (node (ref "U3") (pin "71") (pinfunction "PC7_71") (pintype "bidirectional"))
    )
    (net (code "119") (name "unconnected-(U3-PC9-Pad69)") (class "Default")
      (node (ref "U3") (pin "69") (pinfunction "PC9_69") (pintype "bidirectional"))
    )
    (net (code "120") (name "unconnected-(U3-PC10-Pad22)") (class "Default")
      (node (ref "U3") (pin "22") (pinfunction "PC10_22") (pintype "bidirectional"))
    )
    (net (code "121") (name "unconnected-(U3-PC11-Pad23)") (class "Default")
      (node (ref "U3") (pin "23") (pinfunction "PC11_23") (pintype "bidirectional"))
    )
    (net (code "122") (name "unconnected-(U3-PC13-Pad40)") (class "Default")
      (node (ref "U3") (pin "40") (pinfunction "PC13_40") (pintype "bidirectional"))
    )
    (net (code "123") (name "unconnected-(U3-PD2-Pad68)") (class "Default")
      (node (ref "U3") (pin "68") (pinfunction "PD2_68") (pintype "bidirectional"))
    )
    (net (code "124") (name "unconnected-(U3-PD3-Pad70)") (class "Default")
      (node (ref "U3") (pin "70") (pinfunction "PD3_70") (pintype "bidirectional"))
    )
    (net (code "125") (name "unconnected-(U3-PD5-Pad80)") (class "Default")
      (node (ref "U3") (pin "80") (pinfunction "PD5_80") (pintype "bidirectional"))
    )
    (net (code "126") (name "unconnected-(U3-PD6-Pad81)") (class "Default")
      (node (ref "U3") (pin "81") (pinfunction "PD6_81") (pintype "bidirectional"))
    )
    (net (code "127") (name "unconnected-(U3-PD7-Pad67)") (class "Default")
      (node (ref "U3") (pin "67") (pinfunction "PD7_67") (pintype "bidirectional"))
    )
    (net (code "128") (name "unconnected-(U3-PD8-Pad75)") (class "Default")
      (node (ref "U3") (pin "75") (pinfunction "PD8_75") (pintype "bidirectional"))
    )
    (net (code "129") (name "unconnected-(U3-PD9-Pad74)") (class "Default")
      (node (ref "U3") (pin "74") (pinfunction "PD9_74") (pintype "bidirectional"))
    )
    (net (code "130") (name "unconnected-(U3-PD10-Pad77)") (class "Default")
      (node (ref "U3") (pin "77") (pinfunction "PD10_77") (pintype "bidirectional"))
    )
    (net (code "131") (name "unconnected-(U3-PD11-Pad82)") (class "Default")
      (node (ref "U3") (pin "82") (pinfunction "PD11_82") (pintype "bidirectional"))
    )
    (net (code "132") (name "unconnected-(U3-PD12-Pad66)") (class "Default")
      (node (ref "U3") (pin "66") (pinfunction "PD12_66") (pintype "bidirectional"))
    )
    (net (code "133") (name "unconnected-(U3-PD13-Pad65)") (class "Default")
      (node (ref "U3") (pin "65") (pinfunction "PD13_65") (pintype "bidirectional"))
    )
    (net (code "134") (name "unconnected-(U3-PD14-Pad63)") (class "Default")
      (node (ref "U3") (pin "63") (pinfunction "PD14_63") (pintype "bidirectional"))
    )
    (net (code "135") (name "unconnected-(U3-PD15-Pad76)") (class "Default")
      (node (ref "U3") (pin "76") (pinfunction "PD15_76") (pintype "bidirectional"))
    )
    (net (code "136") (name "unconnected-(U3-PE0-Pad79)") (class "Default")
      (node (ref "U3") (pin "79") (pinfunction "PE0_79") (pintype "bidirectional"))
    )
    (net (code "137") (name "unconnected-(U3-PE1-Pad64)") (class "Default")
      (node (ref "U3") (pin "64") (pinfunction "PE1_64") (pintype "bidirectional"))
    )
    (net (code "138") (name "unconnected-(U3-PE2-Pad78)") (class "Default")
      (node (ref "U3") (pin "78") (pinfunction "PE2_78") (pintype "bidirectional"))
    )
    (net (code "139") (name "unconnected-(U3-PE4-Pad42)") (class "Default")
      (node (ref "U3") (pin "42") (pinfunction "PE4_42") (pintype "bidirectional"))
    )
    (net (code "140") (name "unconnected-(U3-PH0-Pad61)") (class "Default")
      (node (ref "U3") (pin "61") (pinfunction "PH0_61") (pintype "bidirectional"))
    )
    (net (code "141") (name "unconnected-(U3-PH1-Pad62)") (class "Default")
      (node (ref "U3") (pin "62") (pinfunction "PH1_62") (pintype "bidirectional"))
    )
    (net (code "142") (name "unconnected-(U4-PA8-Pad29)") (class "Default")
      (node (ref "U4") (pin "29") (pinfunction "PA8_29") (pintype "bidirectional"))
    )
    (net (code "143") (name "unconnected-(U4-PA15-Pad38)") (class "Default")
      (node (ref "U4") (pin "38") (pinfunction "PA15_38") (pintype "bidirectional"))
    )
    (net (code "144") (name "unconnected-(U4-PB1-Pad19)") (class "Default")
      (node (ref "U4") (pin "19") (pinfunction "PB1_19") (pintype "bidirectional"))
    )
    (net (code "145") (name "unconnected-(U4-PB6-Pad42)") (class "Default")
      (node (ref "U4") (pin "42") (pinfunction "PB6_42") (pintype "bidirectional"))
    )
    (net (code "146") (name "unconnected-(U4-PB9-Pad46)") (class "Default")
      (node (ref "U4") (pin "46") (pinfunction "PB9_46") (pintype "bidirectional"))
    )
    (net (code "147") (name "unconnected-(U4-PC13-Pad2)") (class "Default")
      (node (ref "U4") (pin "2") (pinfunction "PC13_2") (pintype "bidirectional"))
    )
    (net (code "148") (name "unconnected-(U4-PC14-OSC32_IN-Pad3)") (class "Default")
      (node (ref "U4") (pin "3") (pinfunction "PC14-OSC32_IN_3") (pintype "bidirectional"))
    )
    (net (code "149") (name "unconnected-(U4-PC15-OSC32_OUT-Pad4)") (class "Default")
      (node (ref "U4") (pin "4") (pinfunction "PC15-OSC32_OUT_4") (pintype "bidirectional"))
    )
    (net (code "150") (name "unconnected-(U9-INT2-Pad9)") (class "Default")
      (node (ref "U9") (pin "9") (pinfunction "INT2_9") (pintype "bidirectional"))
    )
    (net (code "151") (name "unconnected-(U9-RES3-Pad10)") (class "Default")
      (node (ref "U9") (pin "10") (pinfunction "RES3_10") (pintype "bidirectional"))
    )
    (net (code "152") (name "unconnected-(U9-RES4-Pad11)") (class "Default")
      (node (ref "U9") (pin "11") (pinfunction "RES4_11") (pintype "bidirectional"))
    )
    (net (code "153") (name "unconnected-(U10-ALERT-Pad3)") (class "Default")
      (node (ref "U10") (pin "3") (pinfunction "ALERT_3") (pintype "bidirectional"))
    )
    (net (code "154") (name "unconnected-(U11-ESD1_1-Pad4)") (class "Default")
      (node (ref "U11") (pin "4") (pinfunction "ESD1_1_4") (pintype "bidirectional"))
    )
    (net (code "155") (name "unconnected-(U11-ESD1_2-Pad13)") (class "Default")
      (node (ref "U11") (pin "13") (pinfunction "ESD1_2_13") (pintype "bidirectional"))
    )
    (net (code "156") (name "unconnected-(U11-ESD3-Pad5)") (class "Default")
      (node (ref "U11") (pin "5") (pinfunction "ESD3_5") (pintype "bidirectional"))
    )
  )
)
